# tr02.net
KiCad netlist of a schematic drawn in EAGLE
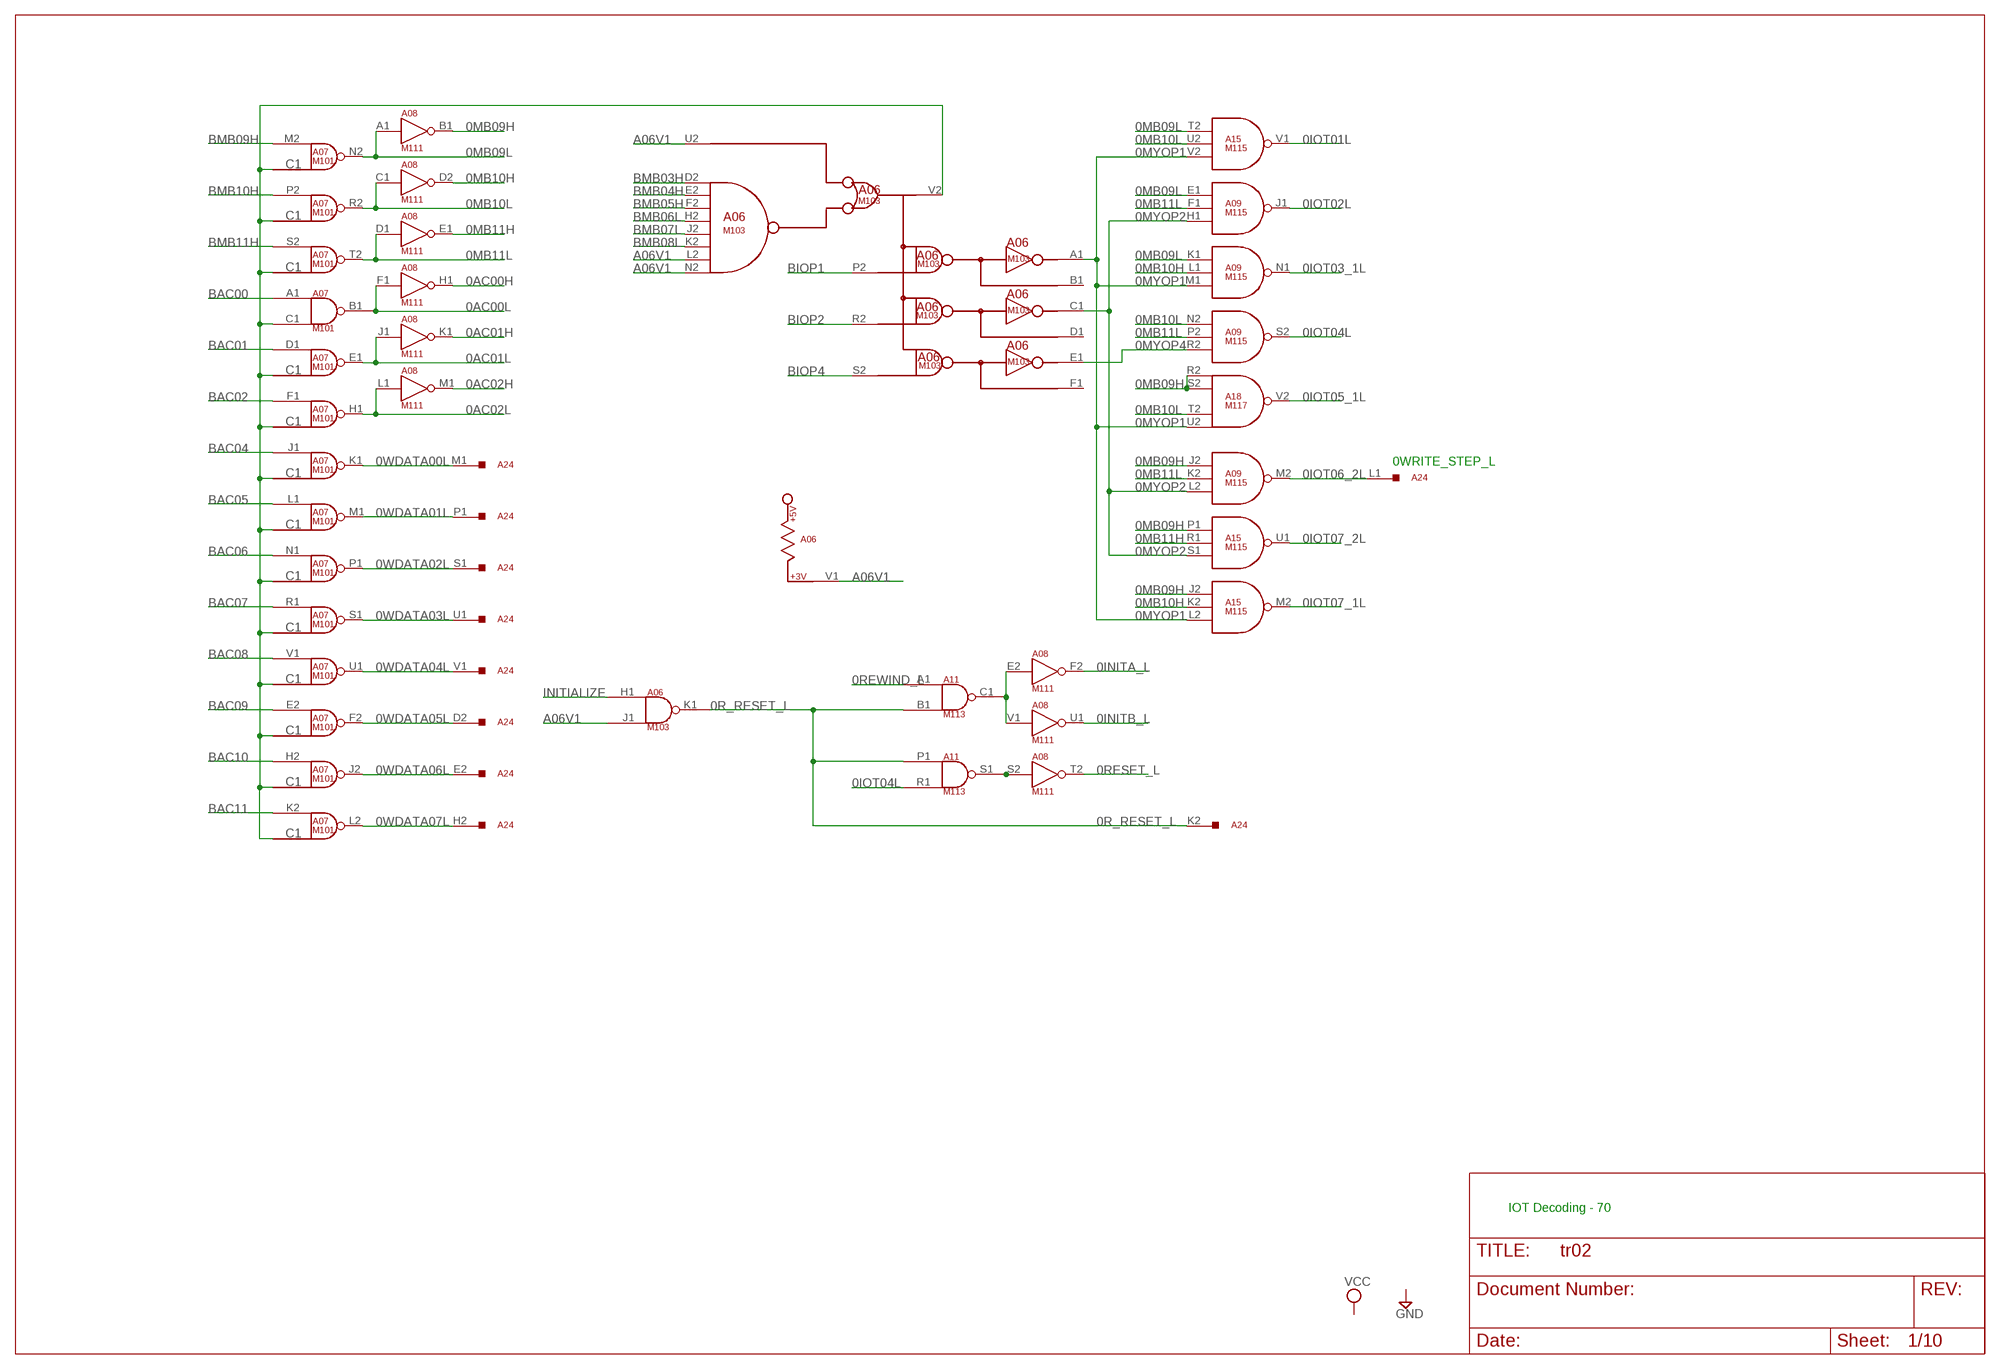
[diagram p0: schematic, sheet 1]
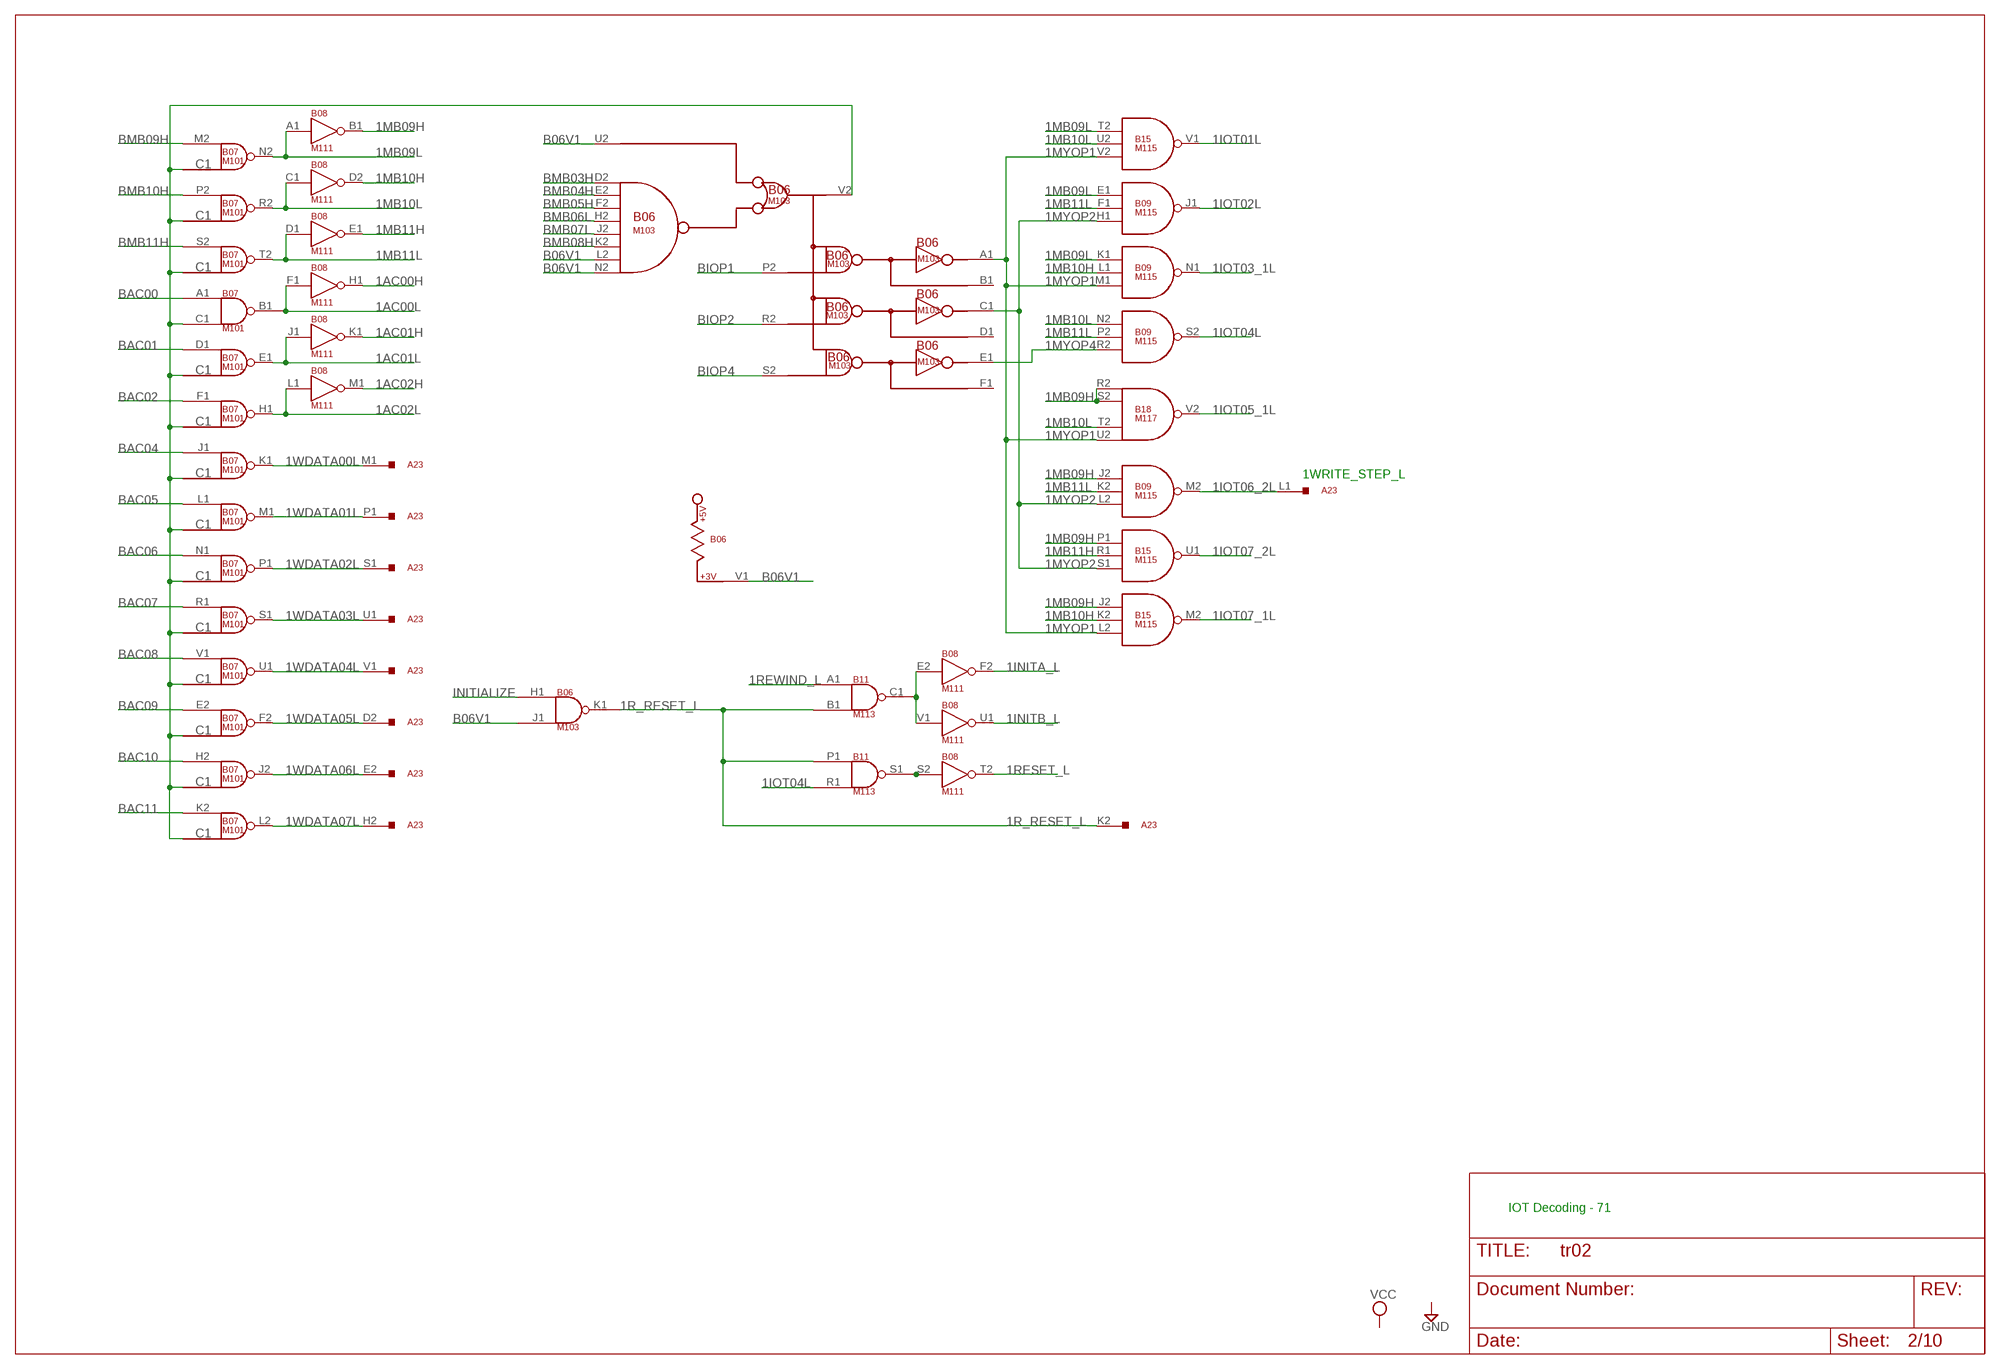
[diagram p1: schematic, sheet 2]
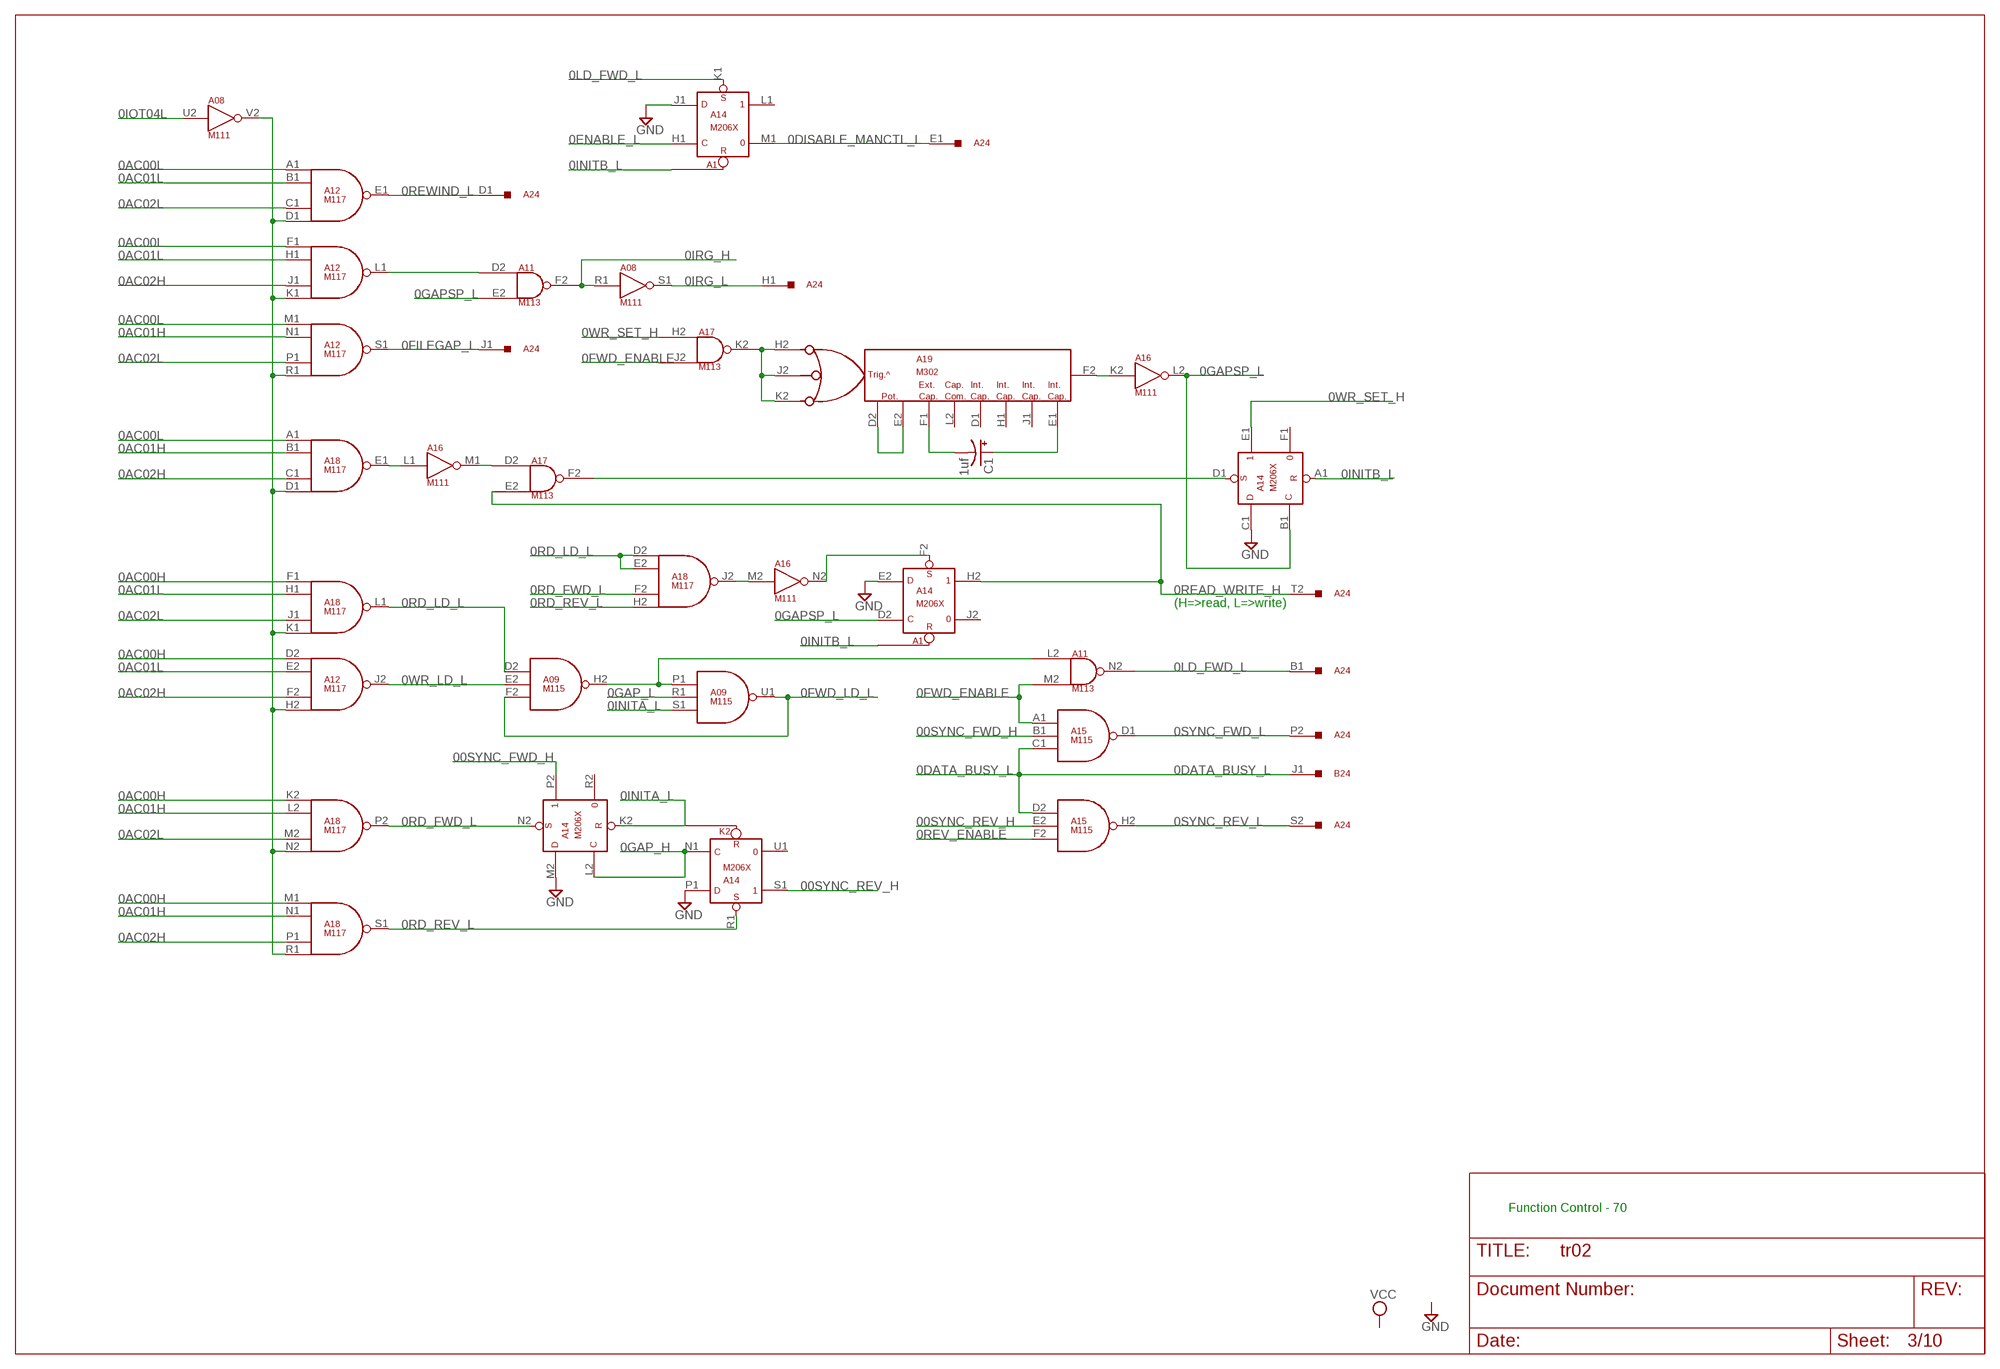
[diagram p2: schematic, sheet 3]
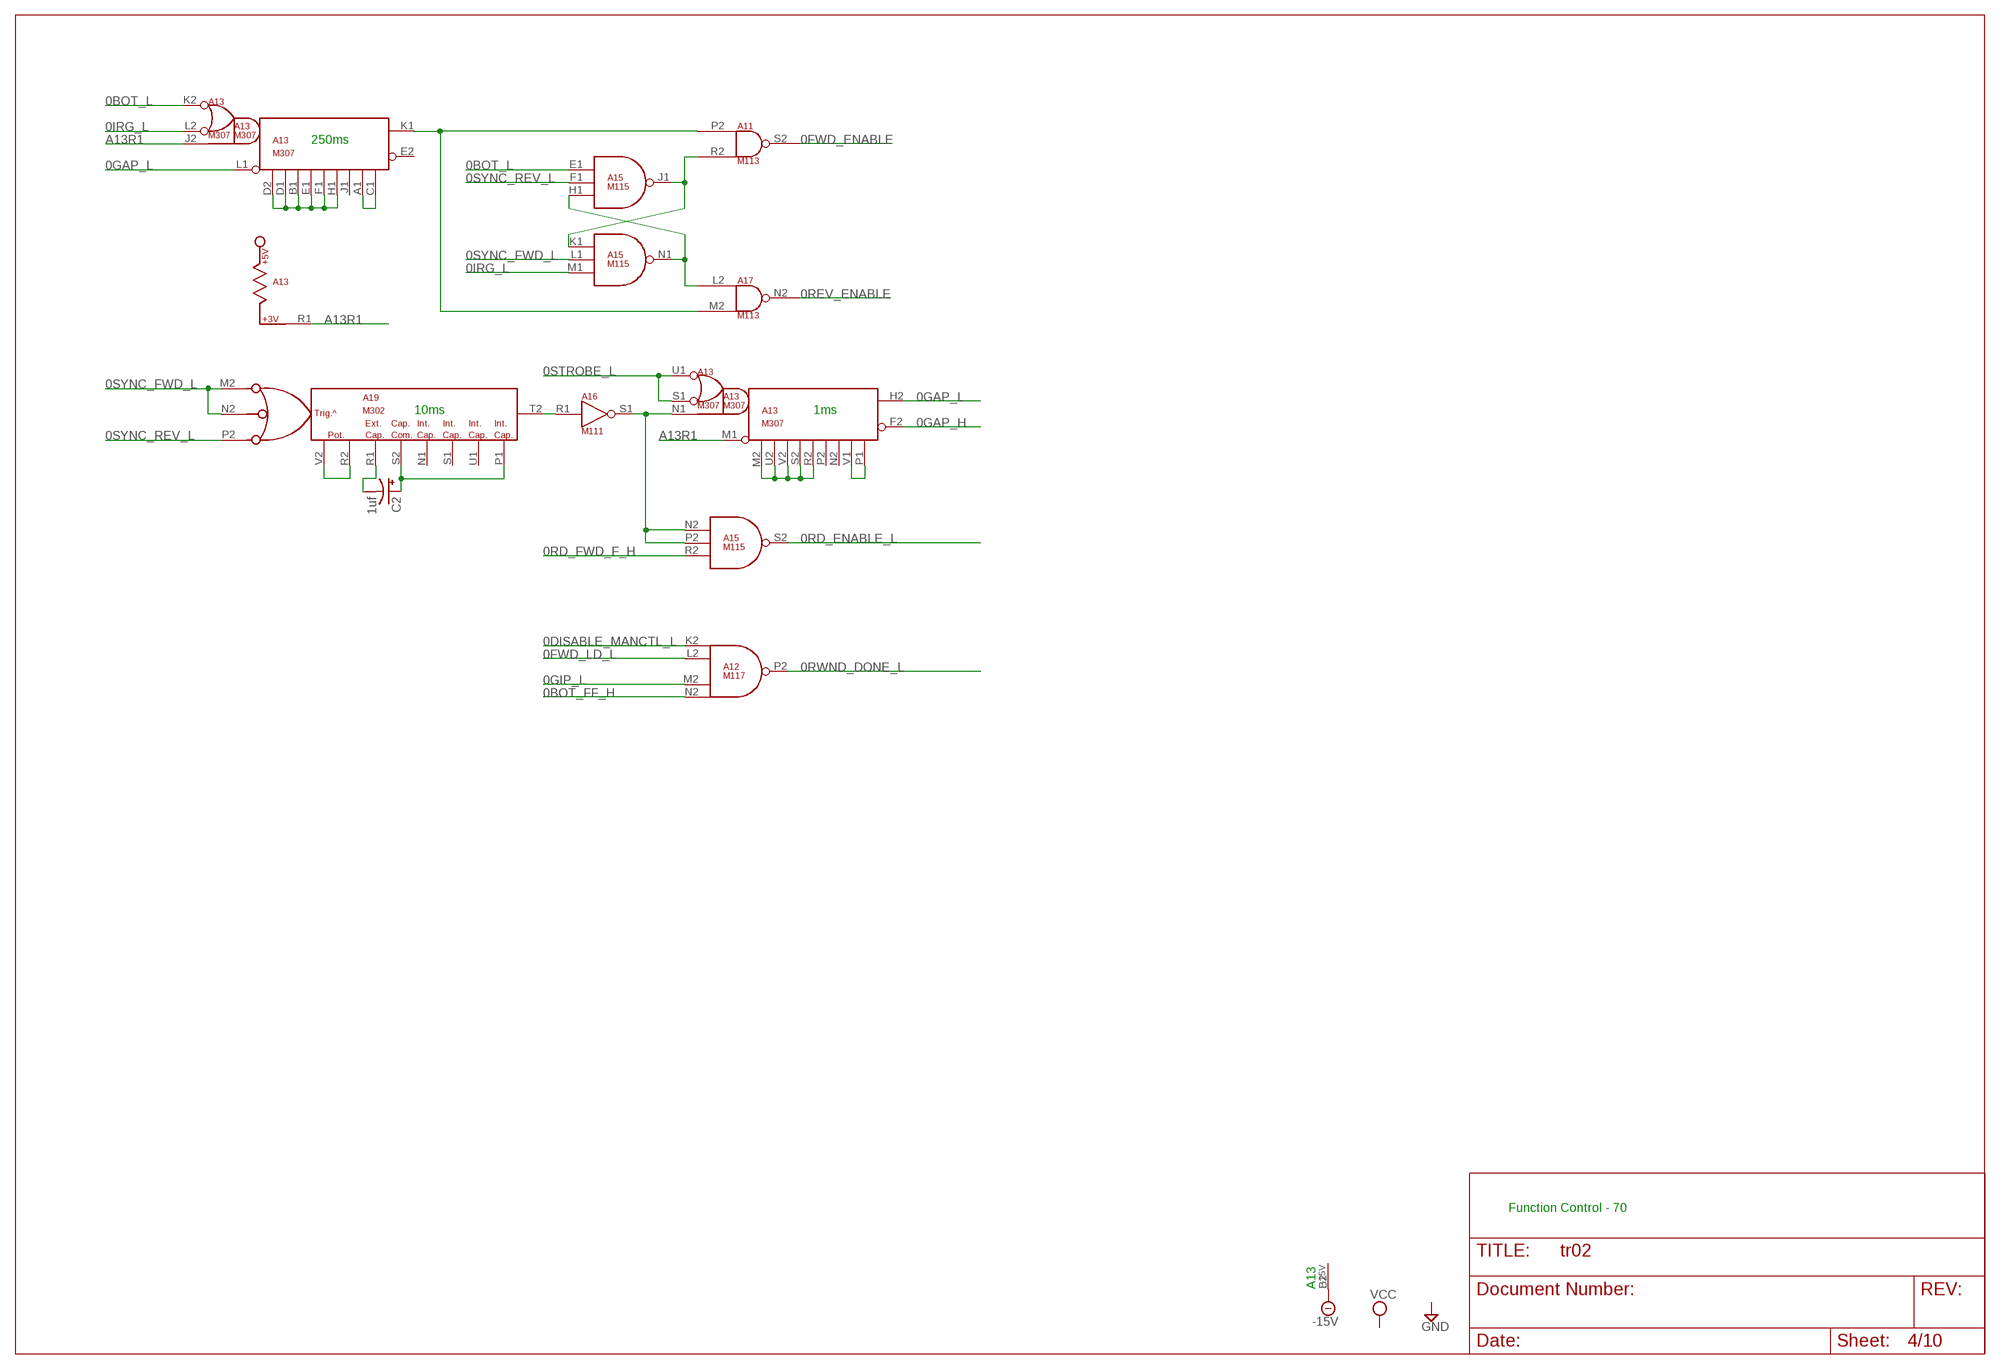
[diagram p3: schematic, sheet 4]
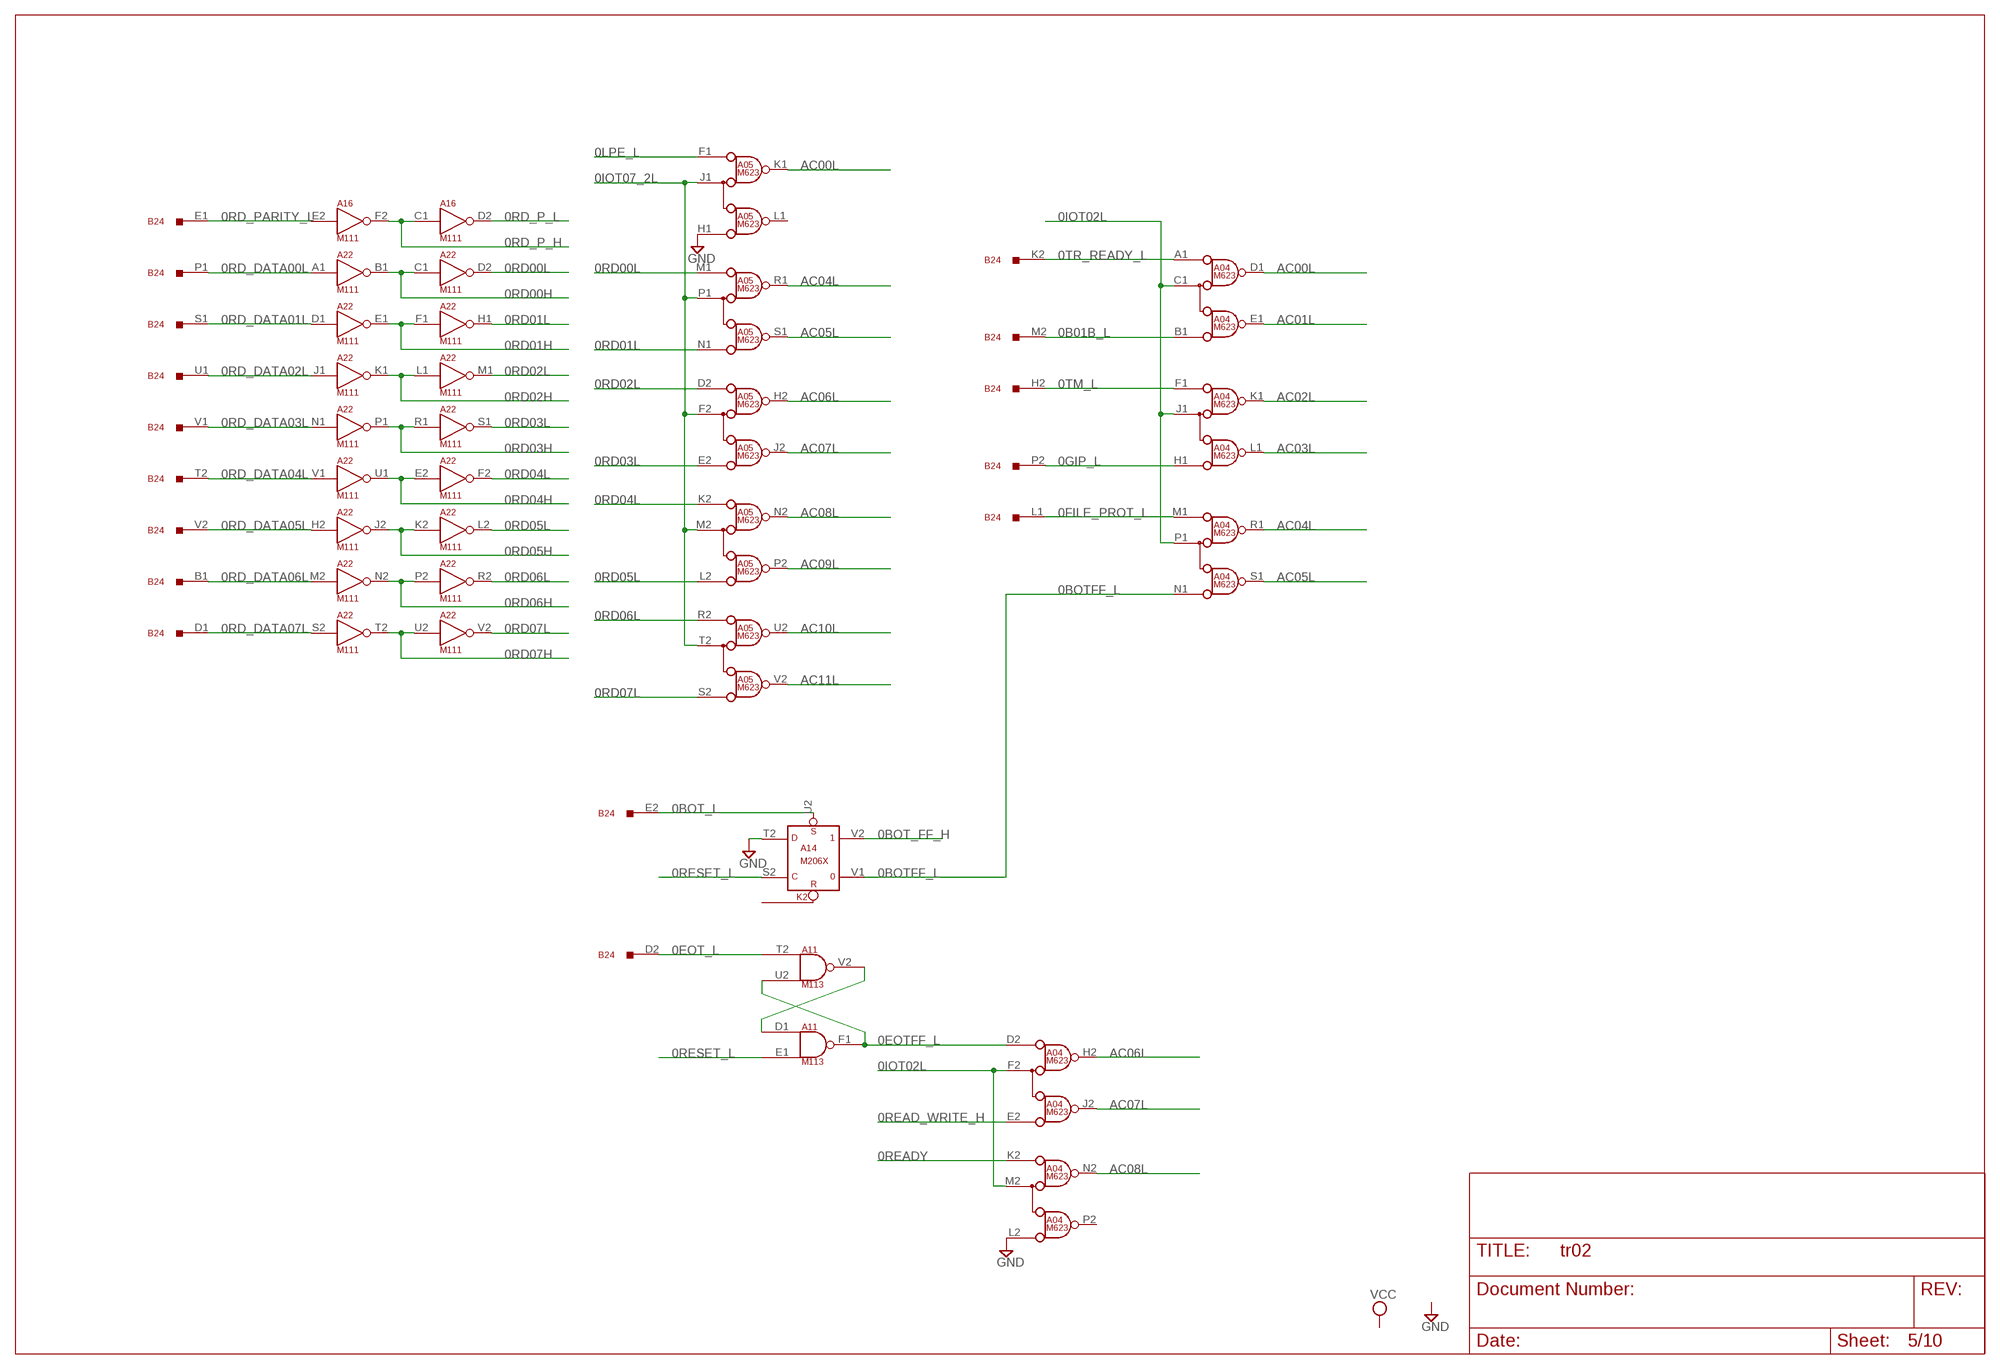
[diagram p4: schematic, sheet 5]
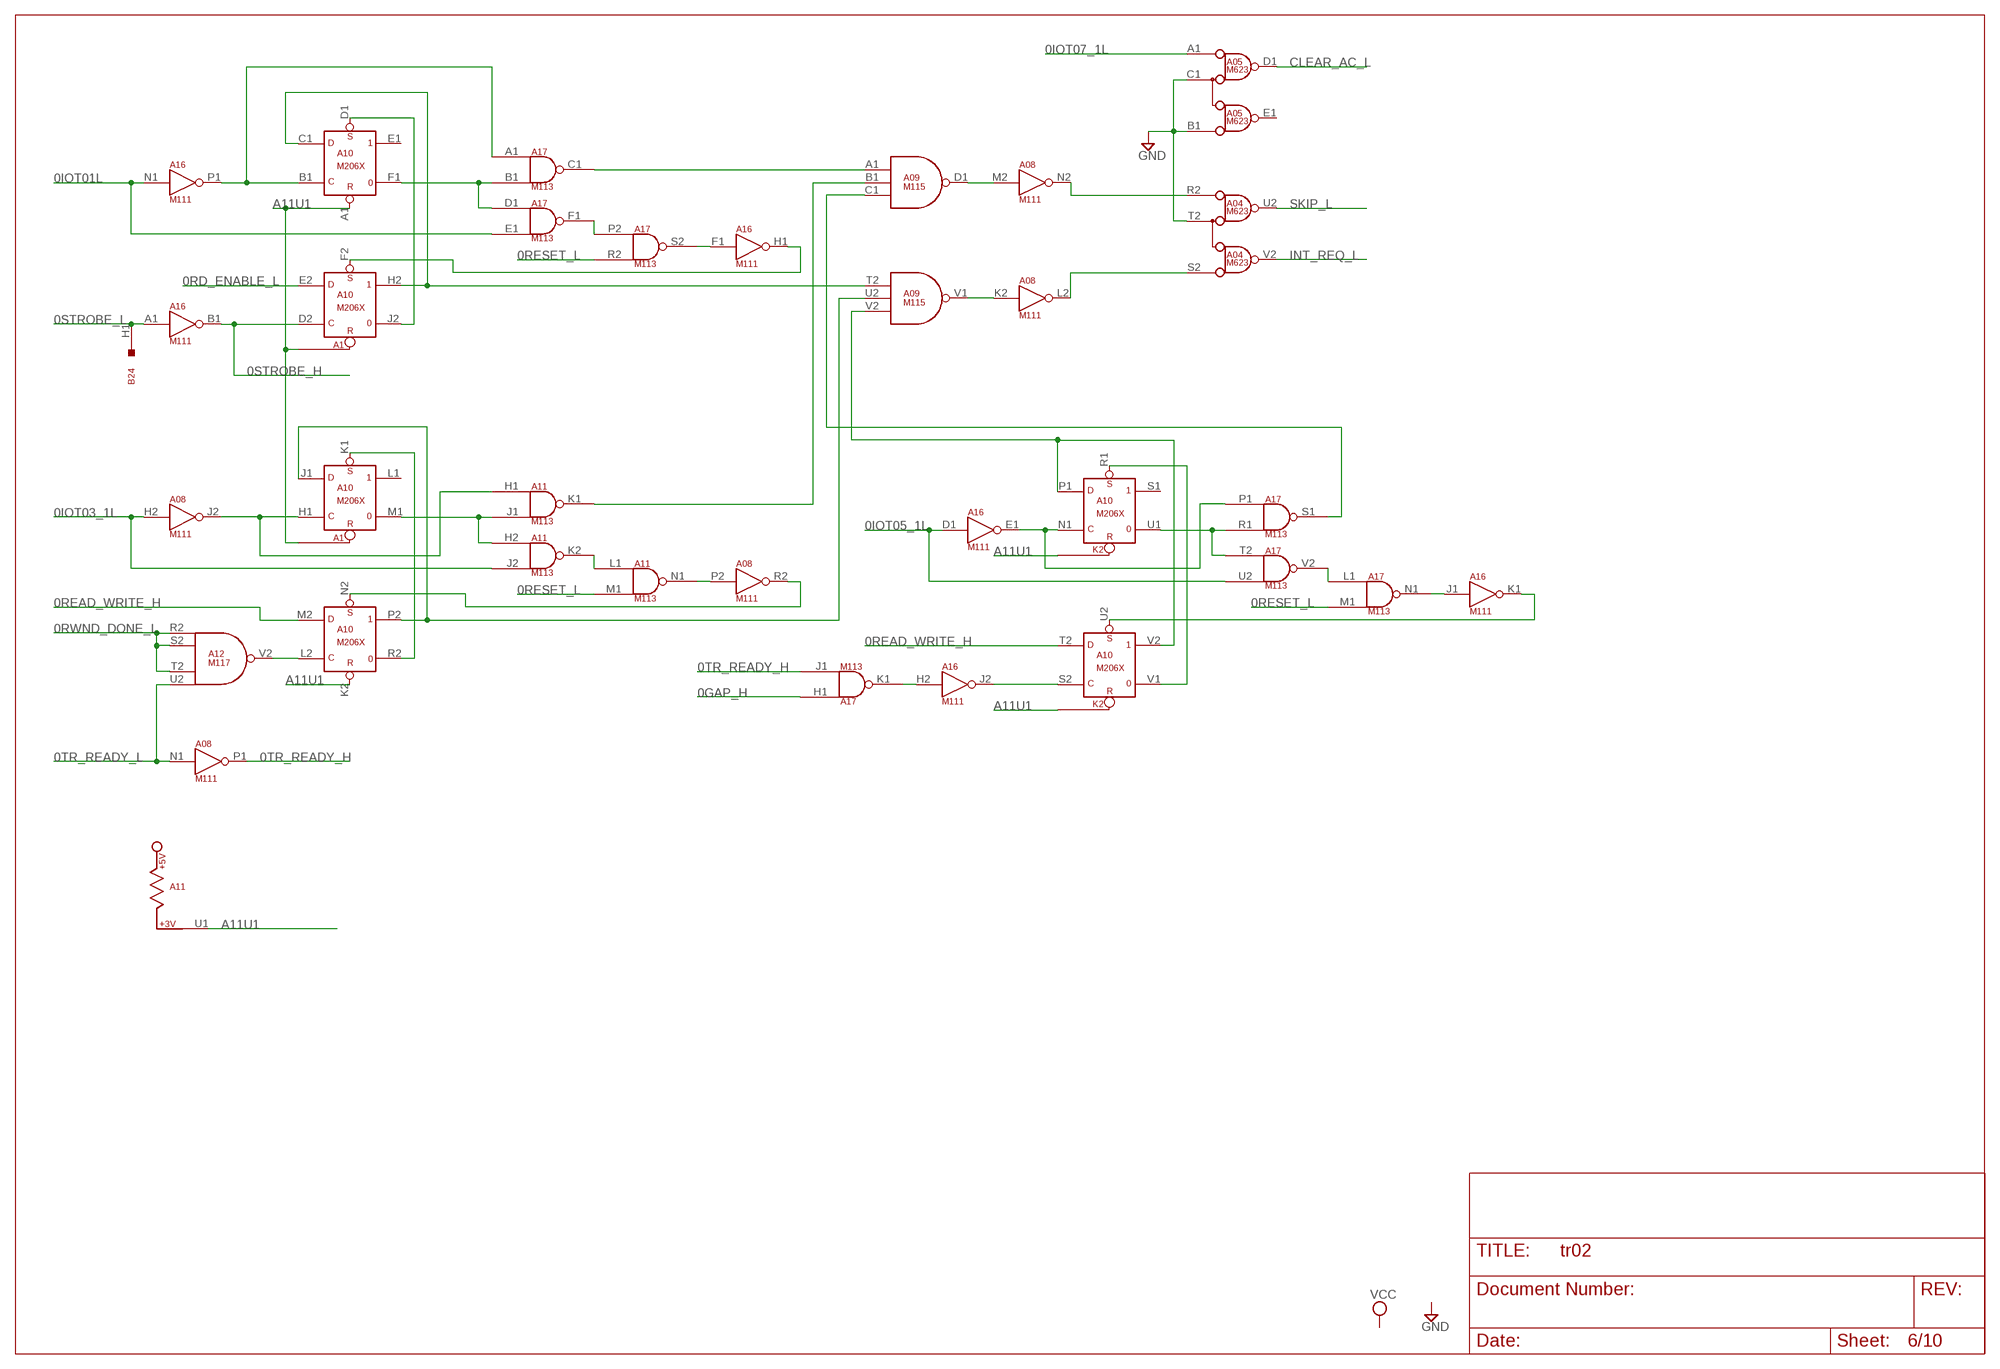
[diagram p5: schematic, sheet 6]
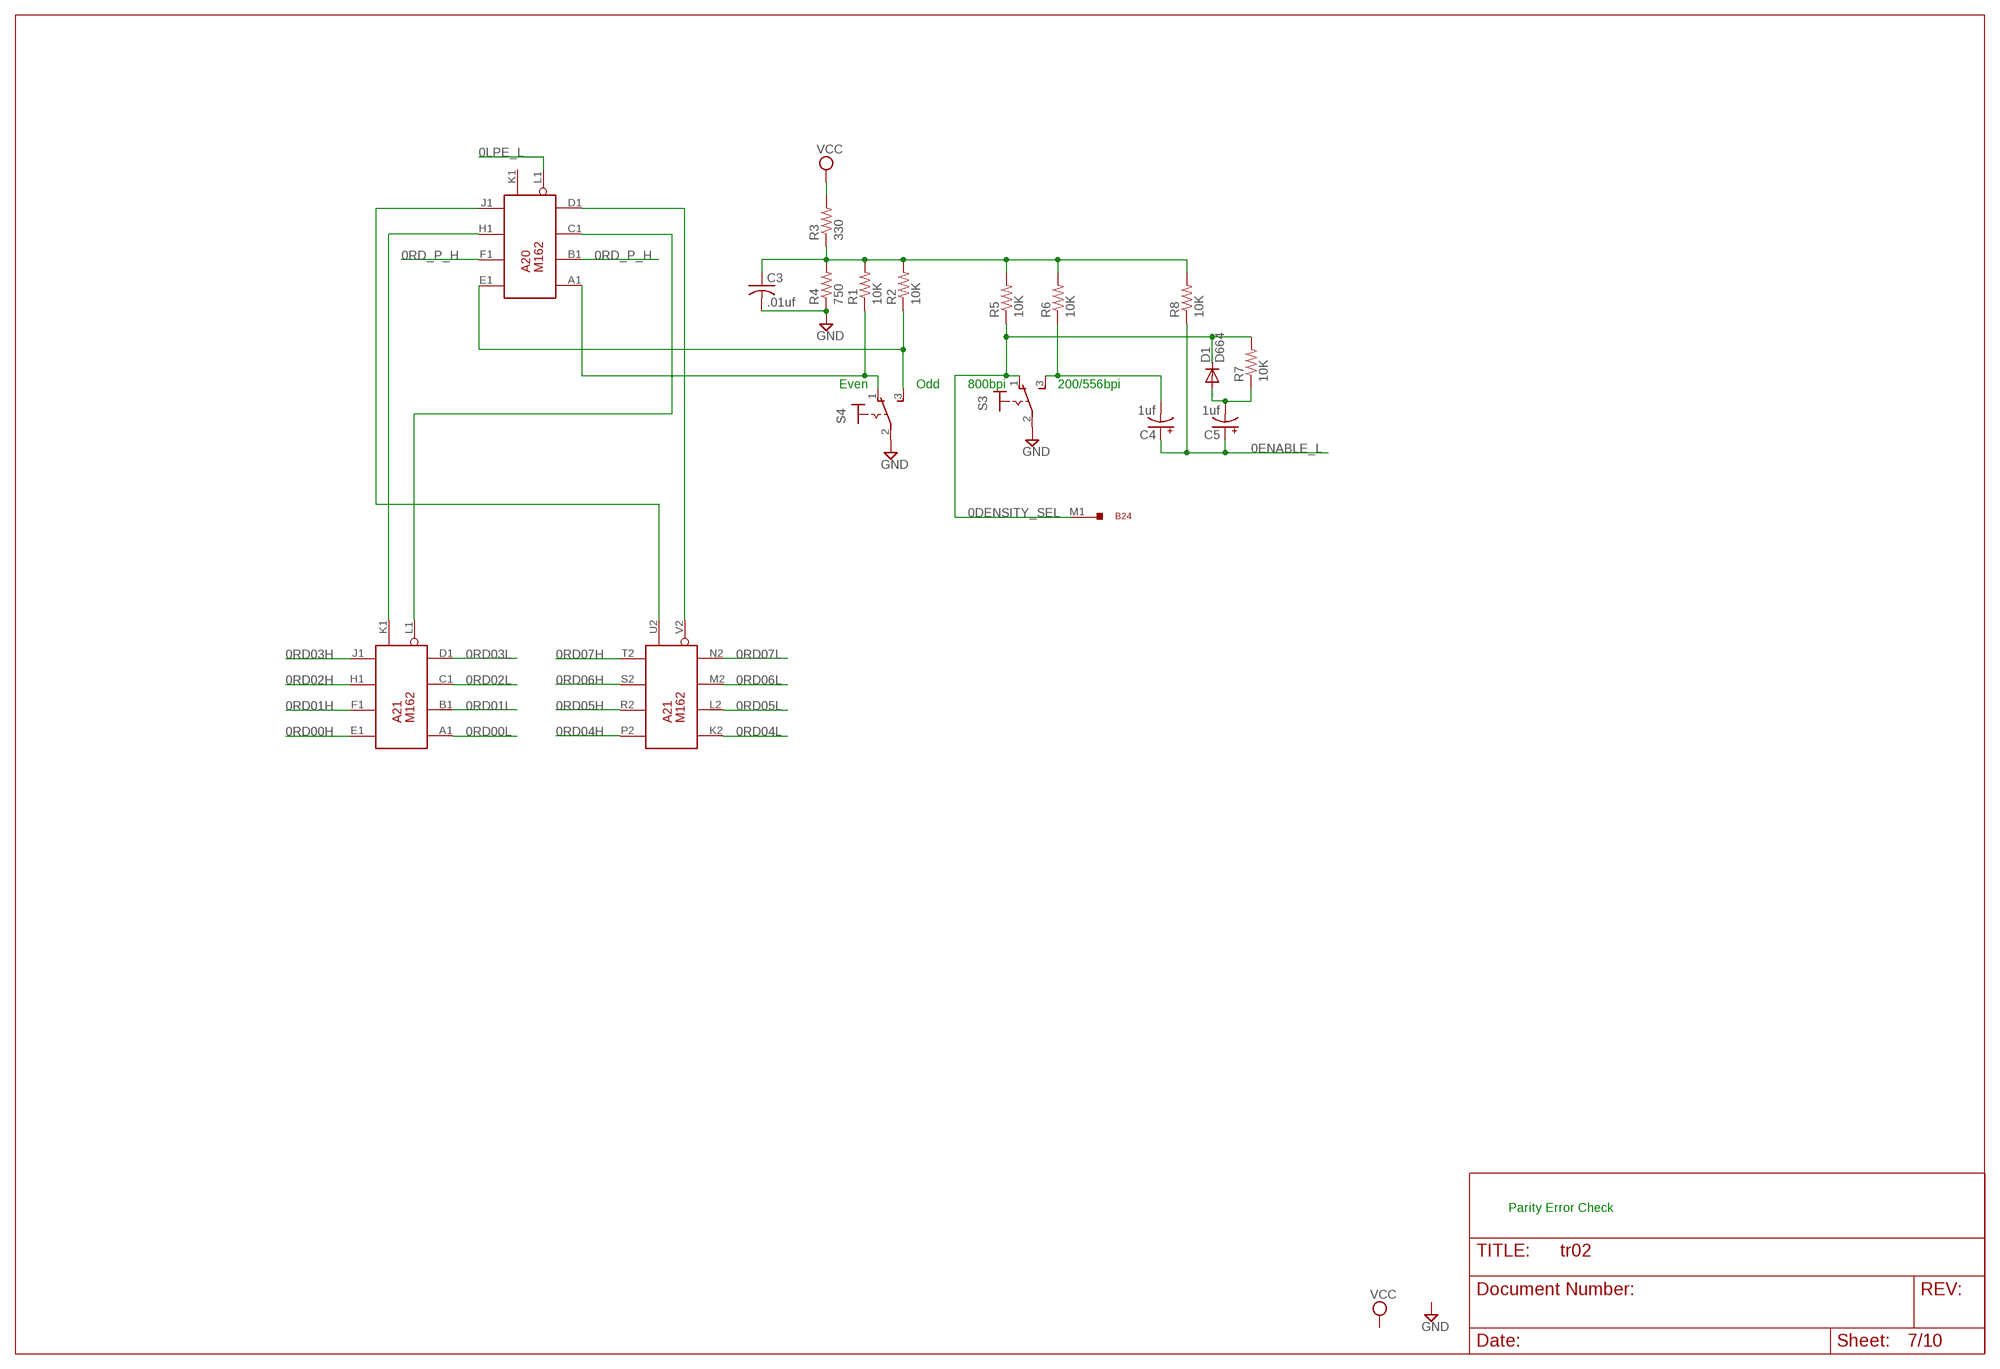
[diagram p6: schematic, sheet 7]
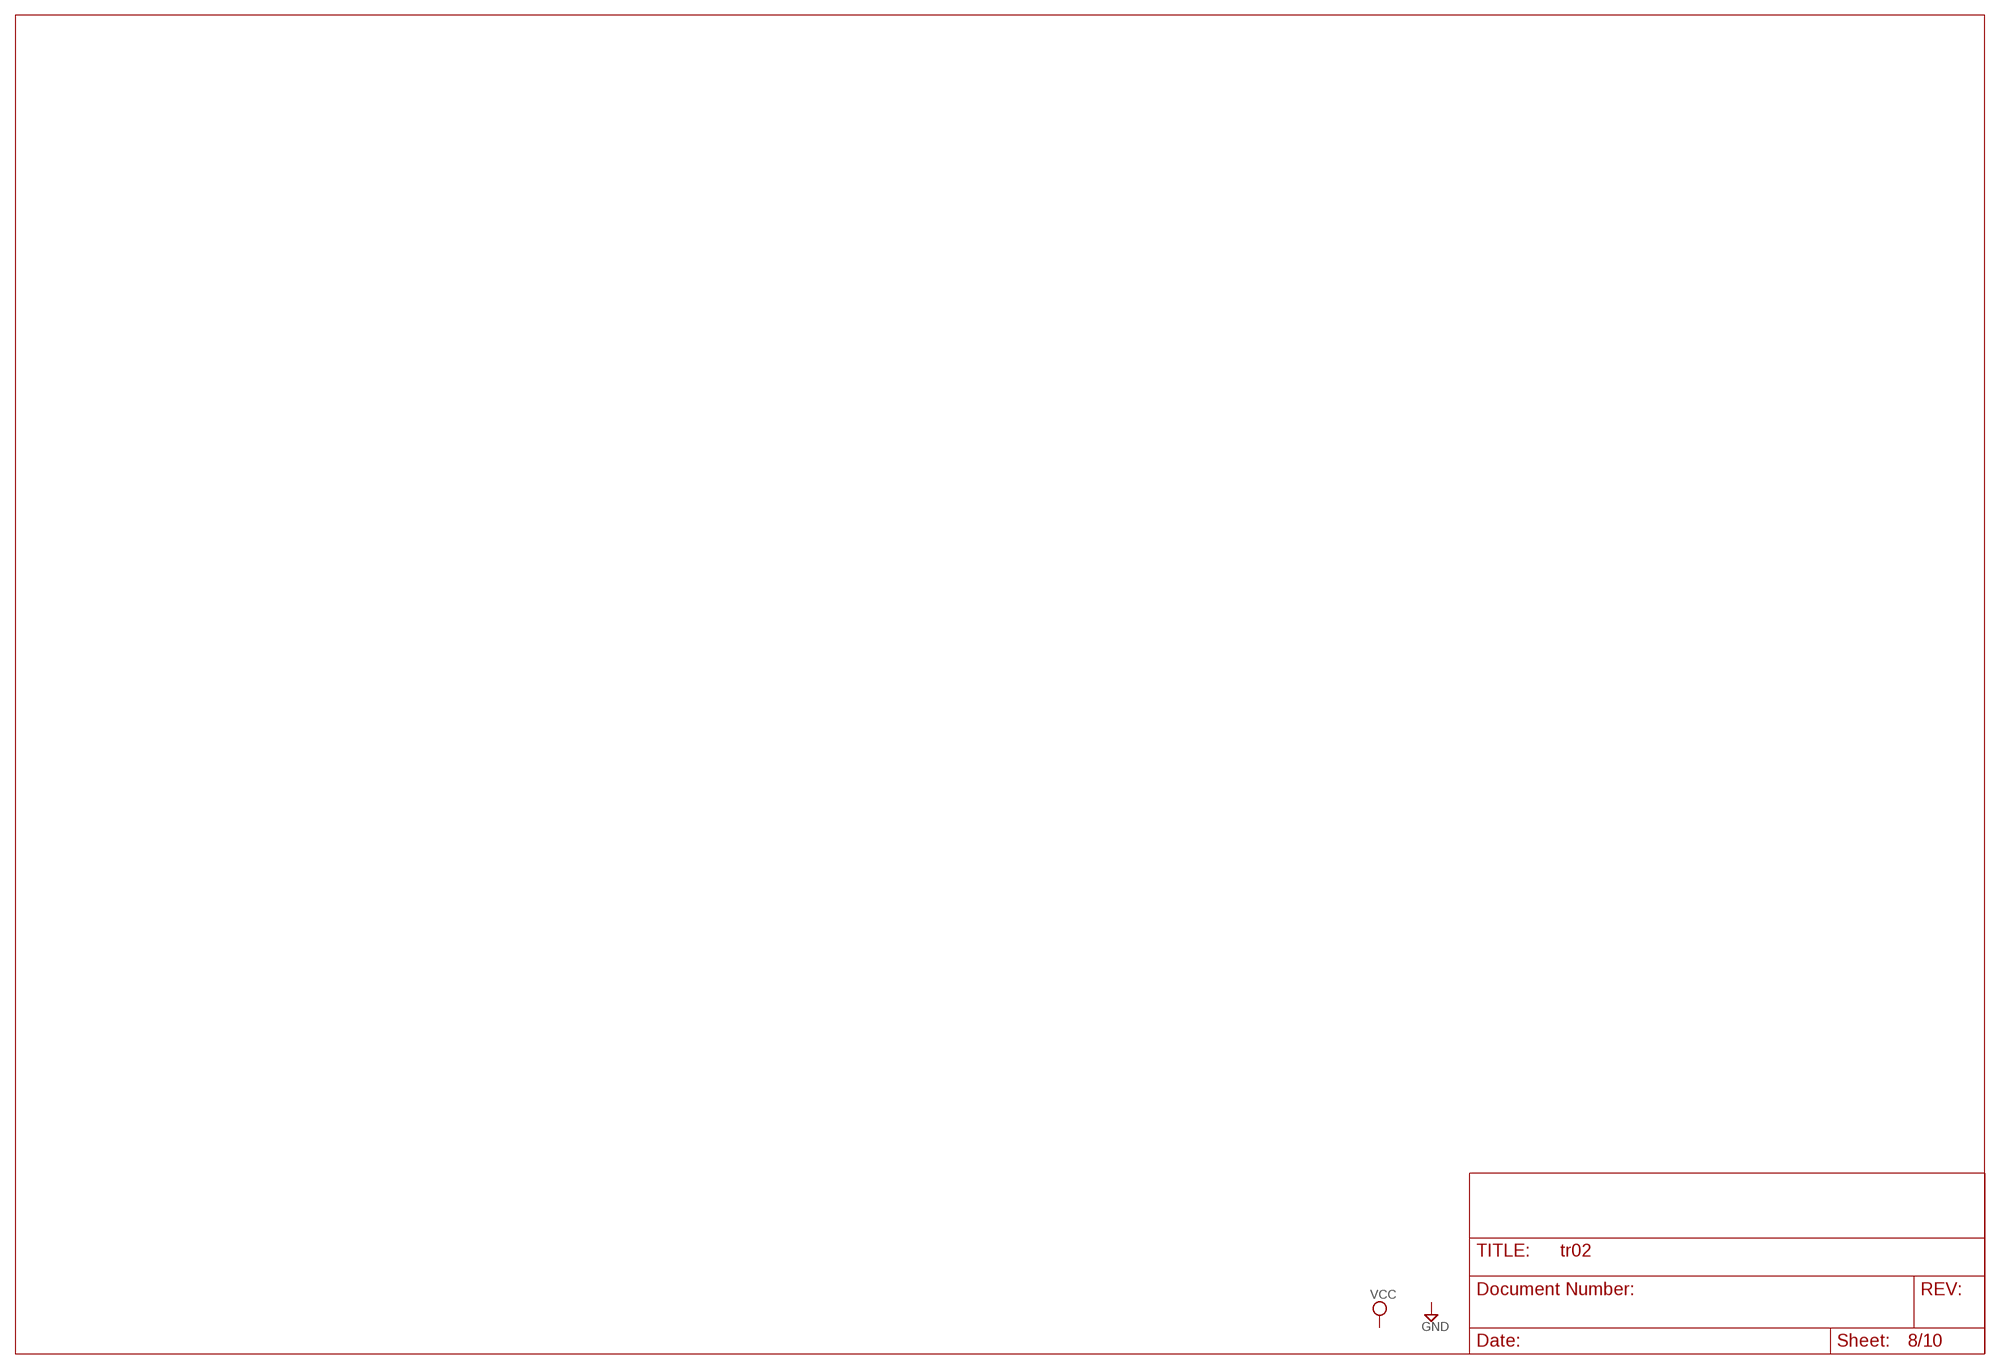
[diagram p7: schematic, sheet 8]
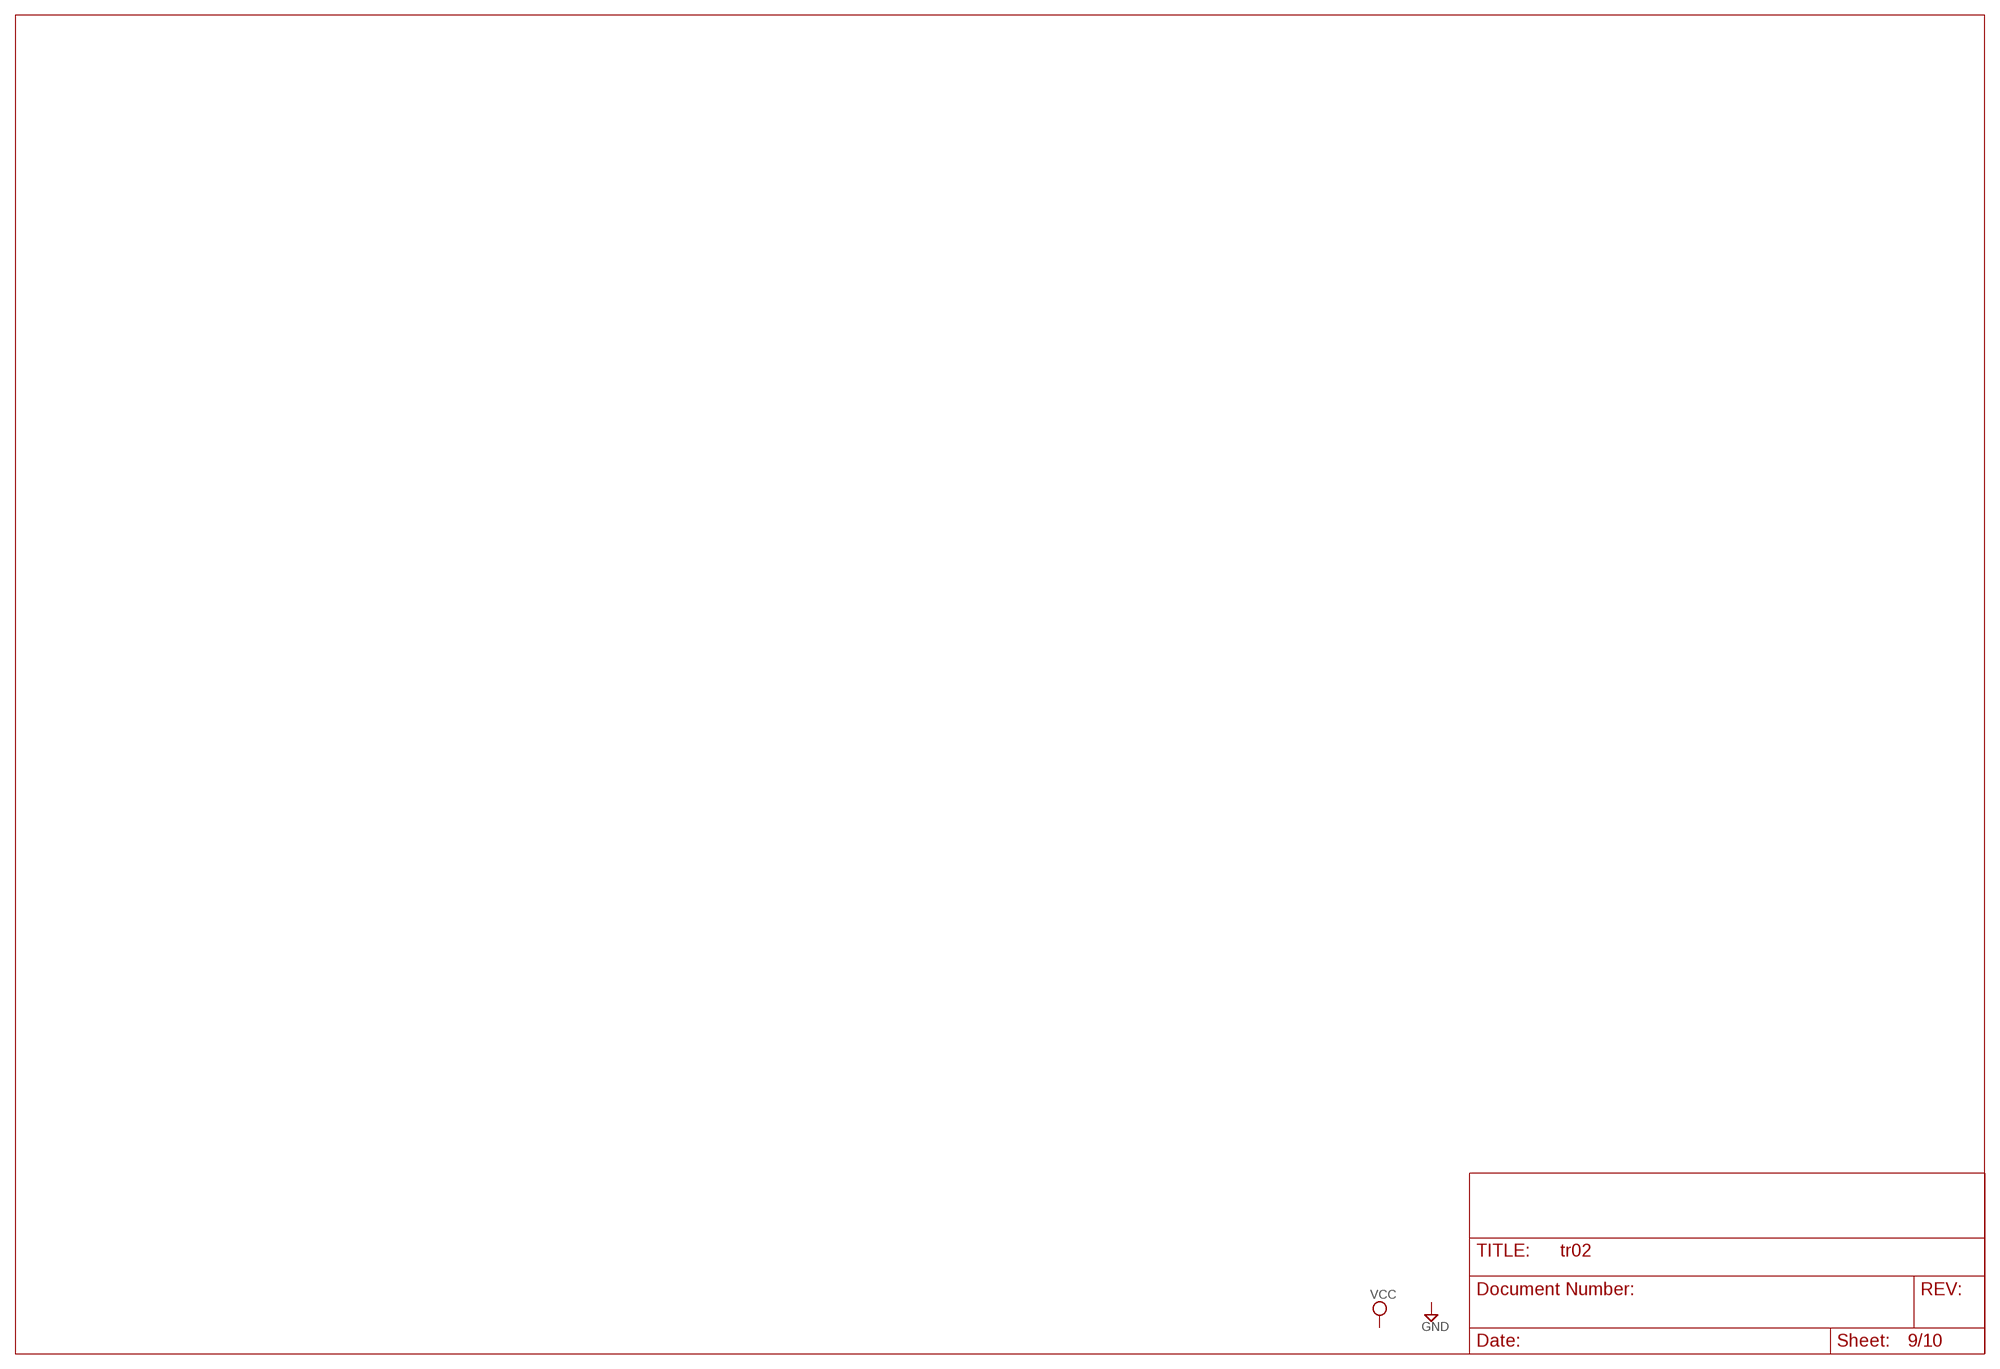
[diagram p8: schematic, sheet 9]
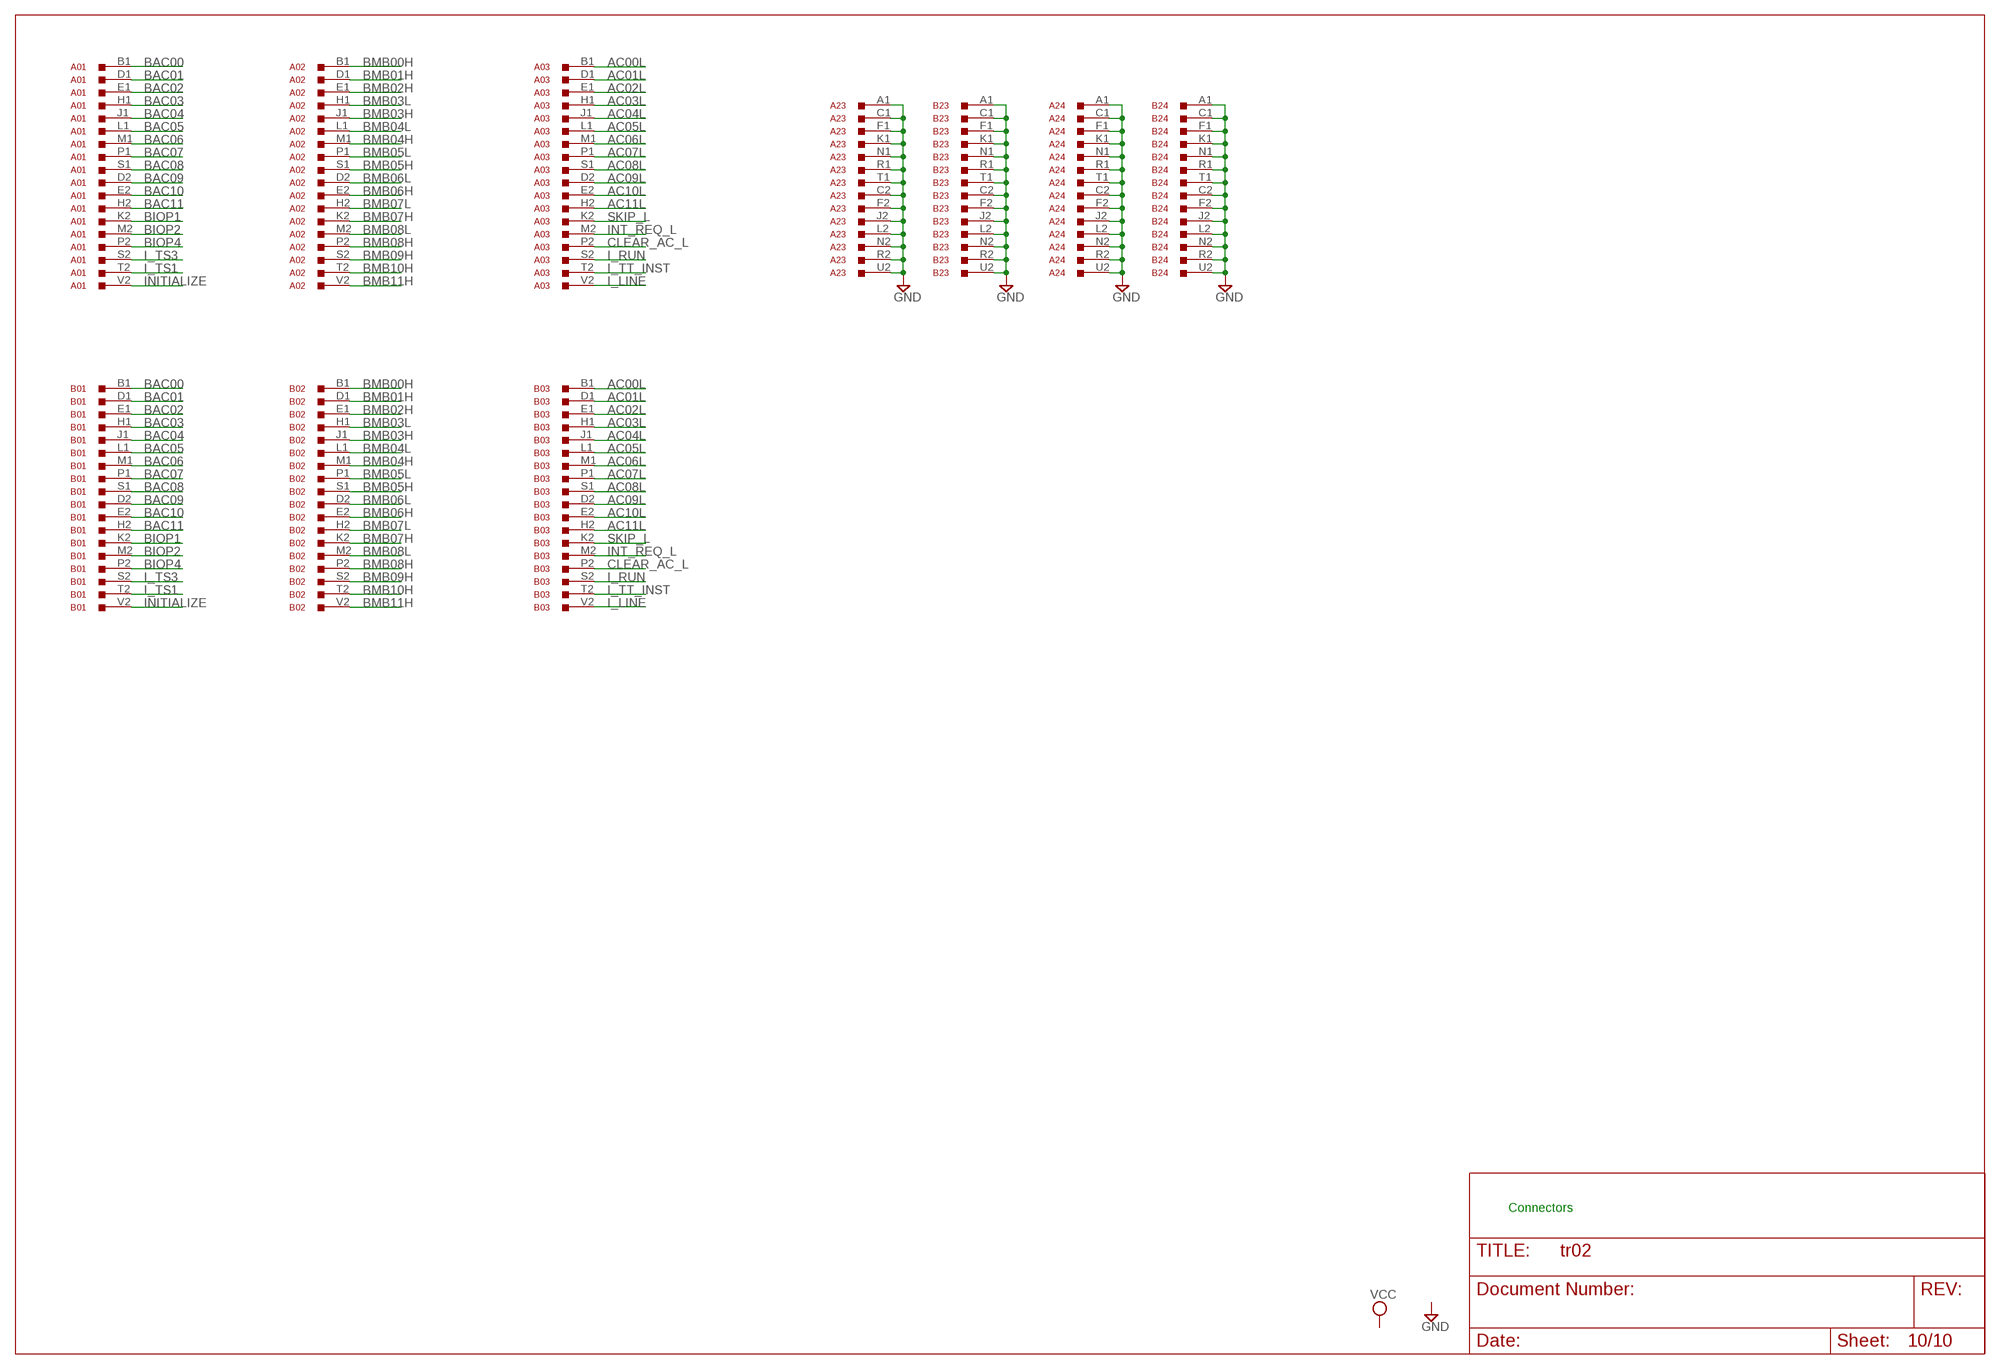
[diagram p9: schematic, sheet 10]

(export (version "E")
  (design (tool "Eeschema 10.0.6"))
  (components
    (comp (ref "A23")
      (value "G784")
      (footprint "eagle-import:H807")
      (libsource (lib "eagle-import") (part "M916"))
    )
    (comp (ref "B06")
      (value "M103")
      (footprint "eagle-import:H807")
      (libsource (lib "eagle-import") (part "M103"))
    )
    (comp (ref "B07")
      (value "M101")
      (footprint "eagle-import:H807")
      (libsource (lib "eagle-import") (part "M101"))
    )
    (comp (ref "B08")
      (value "M111")
      (footprint "eagle-import:H807")
      (libsource (lib "eagle-import") (part "M111"))
    )
    (comp (ref "B09")
      (value "M115")
      (footprint "eagle-import:H807")
      (libsource (lib "eagle-import") (part "M115"))
    )
    (comp (ref "B11")
      (value "M113")
      (footprint "eagle-import:H807")
      (libsource (lib "eagle-import") (part "M113"))
    )
    (comp (ref "B15")
      (value "M115")
      (footprint "eagle-import:H807")
      (libsource (lib "eagle-import") (part "M115"))
    )
    (comp (ref "B18")
      (value "M117")
      (footprint "eagle-import:H807")
      (libsource (lib "eagle-import") (part "M117"))
    )
    (comp (ref "A08")
      (value "M111")
      (footprint "eagle-import:H807")
      (libsource (lib "eagle-import") (part "M111"))
    )
    (comp (ref "A09")
      (value "M115")
      (footprint "eagle-import:H807")
      (libsource (lib "eagle-import") (part "M115"))
    )
    (comp (ref "A11")
      (value "M113")
      (footprint "eagle-import:H807")
      (libsource (lib "eagle-import") (part "M113"))
    )
    (comp (ref "A12")
      (value "M117")
      (footprint "eagle-import:H807")
      (libsource (lib "eagle-import") (part "M117"))
    )
    (comp (ref "A14")
      (value "M206X")
      (footprint "eagle-import:H807")
      (libsource (lib "eagle-import") (part "M206X"))
    )
    (comp (ref "A15")
      (value "M115")
      (footprint "eagle-import:H807")
      (libsource (lib "eagle-import") (part "M115"))
    )
    (comp (ref "A16")
      (value "M111")
      (footprint "eagle-import:H807")
      (libsource (lib "eagle-import") (part "M111"))
    )
    (comp (ref "A17")
      (value "M113")
      (footprint "eagle-import:H807")
      (libsource (lib "eagle-import") (part "M113"))
    )
    (comp (ref "A18")
      (value "M117")
      (footprint "eagle-import:H807")
      (libsource (lib "eagle-import") (part "M117"))
    )
    (comp (ref "A19")
      (value "M302")
      (footprint "eagle-import:H807")
      (libsource (lib "eagle-import") (part "M302"))
    )
    (comp (ref "A24")
      (value "G784")
      (footprint "eagle-import:H807")
      (libsource (lib "eagle-import") (part "M916"))
    )
    (comp (ref "B24")
      (value "G784")
      (footprint "eagle-import:H807")
      (libsource (lib "eagle-import") (part "M916"))
    )
    (comp (ref "C1")
      (value "1uf")
      (footprint "eagle-import:E22-6")
      (libsource (lib "eagle-import") (part "CPOL-USE22-6AXIAL"))
    )
    (comp (ref "A20")
      (value "M162")
      (footprint "eagle-import:H807")
      (libsource (lib "eagle-import") (part "M162"))
    )
    (comp (ref "A21")
      (value "M162")
      (footprint "eagle-import:H807")
      (libsource (lib "eagle-import") (part "M162"))
    )
    (comp (ref "C3")
      (value ".01uf")
      (footprint "eagle-import:C050-025X075")
      (libsource (lib "eagle-import") (part "C-US050-025X075"))
    )
    (comp (ref "C4")
      (value "1uf")
      (footprint "eagle-import:E22-6")
      (libsource (lib "eagle-import") (part "CPOL-USE22-6AXIAL"))
    )
    (comp (ref "C5")
      (value "1uf")
      (footprint "eagle-import:E22-6")
      (libsource (lib "eagle-import") (part "CPOL-USE22-6AXIAL"))
    )
    (comp (ref "D1")
      (value "D664")
      (footprint "eagle-import:DO35-10")
      (libsource (lib "eagle-import") (part "1N4148DO35-10"))
    )
    (comp (ref "R1")
      (value "10K")
      (footprint "eagle-import:0207_10")
      (libsource (lib "eagle-import") (part "R-US_0207/10"))
    )
    (comp (ref "R2")
      (value "10K")
      (footprint "eagle-import:0207_10")
      (libsource (lib "eagle-import") (part "R-US_0207/10"))
    )
    (comp (ref "R3")
      (value "330")
      (footprint "eagle-import:0207_10")
      (libsource (lib "eagle-import") (part "R-US_0207/10"))
    )
    (comp (ref "R4")
      (value "750")
      (footprint "eagle-import:0207_10")
      (libsource (lib "eagle-import") (part "R-US_0207/10"))
    )
    (comp (ref "R5")
      (value "10K")
      (footprint "eagle-import:0207_10")
      (libsource (lib "eagle-import") (part "R-US_0207/10"))
    )
    (comp (ref "R6")
      (value "10K")
      (footprint "eagle-import:0207_10")
      (libsource (lib "eagle-import") (part "R-US_0207/10"))
    )
    (comp (ref "R7")
      (value "10K")
      (footprint "eagle-import:0207_10")
      (libsource (lib "eagle-import") (part "R-US_0207/10"))
    )
    (comp (ref "R8")
      (value "10K")
      (footprint "eagle-import:0207_10")
      (libsource (lib "eagle-import") (part "R-US_0207/10"))
    )
    (comp (ref "S3")
      (value "320-916")
      (footprint "eagle-import:320-916")
      (libsource (lib "eagle-import") (part "320-916"))
    )
    (comp (ref "S4")
      (value "320-916")
      (footprint "eagle-import:320-916")
      (libsource (lib "eagle-import") (part "320-916"))
    )
    (comp (ref "A04")
      (value "M623")
      (footprint "eagle-import:H807")
      (libsource (lib "eagle-import") (part "M623"))
    )
    (comp (ref "A05")
      (value "M623")
      (footprint "eagle-import:H807")
      (libsource (lib "eagle-import") (part "M623"))
    )
    (comp (ref "A10")
      (value "M206X")
      (footprint "eagle-import:H807")
      (libsource (lib "eagle-import") (part "M206X"))
    )
    (comp (ref "A01")
      (value "M903")
      (footprint "eagle-import:H807")
      (libsource (lib "eagle-import") (part "M903"))
    )
    (comp (ref "A02")
      (value "M903")
      (footprint "eagle-import:H807")
      (libsource (lib "eagle-import") (part "M903"))
    )
    (comp (ref "A03")
      (value "M903")
      (footprint "eagle-import:H807")
      (libsource (lib "eagle-import") (part "M903"))
    )
    (comp (ref "B01")
      (value "M903")
      (footprint "eagle-import:H807")
      (libsource (lib "eagle-import") (part "M903"))
    )
    (comp (ref "B02")
      (value "M903")
      (footprint "eagle-import:H807")
      (libsource (lib "eagle-import") (part "M903"))
    )
    (comp (ref "B03")
      (value "M903")
      (footprint "eagle-import:H807")
      (libsource (lib "eagle-import") (part "M903"))
    )
    (comp (ref "B23")
      (value "G784")
      (footprint "eagle-import:H807")
      (libsource (lib "eagle-import") (part "M916"))
    )
    (comp (ref "A06")
      (value "M103")
      (footprint "eagle-import:H807")
      (libsource (lib "eagle-import") (part "M103"))
    )
    (comp (ref "A07")
      (value "M101")
      (footprint "eagle-import:H807")
      (libsource (lib "eagle-import") (part "M101"))
    )
    (comp (ref "A13")
      (value "M307")
      (footprint "eagle-import:H807")
      (libsource (lib "eagle-import") (part "M307"))
    )
    (comp (ref "C2")
      (value "1uf")
      (footprint "eagle-import:E22-6")
      (libsource (lib "eagle-import") (part "CPOL-USE22-6AXIAL"))
    )
    (comp (ref "A22")
      (value "M111")
      (footprint "eagle-import:H807")
      (libsource (lib "eagle-import") (part "M111"))
    )
  )
  (nets
    (net (code "1") (name "-15V") (class "Default")
      (node (ref "A13") (pin "B2") (pinfunction "-15V_B2") (pintype "power_in"))
    )
    (net (code "2") (name "0AC00H") (class "Default")
      (node (ref "A08") (pin "H1") (pinfunction "OUT_H1") (pintype "output"))
      (node (ref "A12") (pin "D2") (pinfunction "IN1_D2") (pintype "input"))
      (node (ref "A18") (pin "F1") (pinfunction "IN1_F1") (pintype "input"))
      (node (ref "A18") (pin "K2") (pinfunction "IN1_K2") (pintype "input"))
      (node (ref "A18") (pin "M1") (pinfunction "IN1_M1") (pintype "input"))
    )
    (net (code "3") (name "0AC00L") (class "Default")
      (node (ref "A07") (pin "B1") (pinfunction "OUT_B1") (pintype "output"))
      (node (ref "A08") (pin "F1") (pinfunction "IN_F1") (pintype "input"))
      (node (ref "A12") (pin "A1") (pinfunction "IN1_A1") (pintype "input"))
      (node (ref "A12") (pin "F1") (pinfunction "IN1_F1") (pintype "input"))
      (node (ref "A12") (pin "M1") (pinfunction "IN1_M1") (pintype "input"))
      (node (ref "A18") (pin "A1") (pinfunction "IN1_A1") (pintype "input"))
    )
    (net (code "4") (name "0AC01H") (class "Default")
      (node (ref "A08") (pin "K1") (pinfunction "OUT_K1") (pintype "output"))
      (node (ref "A12") (pin "N1") (pinfunction "IN2_N1") (pintype "input"))
      (node (ref "A18") (pin "B1") (pinfunction "IN2_B1") (pintype "input"))
      (node (ref "A18") (pin "L2") (pinfunction "IN2_L2") (pintype "input"))
      (node (ref "A18") (pin "N1") (pinfunction "IN2_N1") (pintype "input"))
    )
    (net (code "5") (name "0AC01L") (class "Default")
      (node (ref "A07") (pin "E1") (pinfunction "OUT_E1") (pintype "output"))
      (node (ref "A08") (pin "J1") (pinfunction "IN_J1") (pintype "input"))
      (node (ref "A12") (pin "B1") (pinfunction "IN2_B1") (pintype "input"))
      (node (ref "A12") (pin "E2") (pinfunction "IN2_E2") (pintype "input"))
      (node (ref "A12") (pin "H1") (pinfunction "IN2_H1") (pintype "input"))
      (node (ref "A18") (pin "H1") (pinfunction "IN2_H1") (pintype "input"))
    )
    (net (code "6") (name "0AC02H") (class "Default")
      (node (ref "A08") (pin "M1") (pinfunction "OUT_M1") (pintype "output"))
      (node (ref "A12") (pin "F2") (pinfunction "IN3_F2") (pintype "input"))
      (node (ref "A12") (pin "J1") (pinfunction "IN3_J1") (pintype "input"))
      (node (ref "A18") (pin "C1") (pinfunction "IN3_C1") (pintype "input"))
      (node (ref "A18") (pin "P1") (pinfunction "IN3_P1") (pintype "input"))
    )
    (net (code "7") (name "0AC02L") (class "Default")
      (node (ref "A07") (pin "H1") (pinfunction "OUT_H1") (pintype "output"))
      (node (ref "A08") (pin "L1") (pinfunction "IN_L1") (pintype "input"))
      (node (ref "A12") (pin "C1") (pinfunction "IN3_C1") (pintype "input"))
      (node (ref "A12") (pin "P1") (pinfunction "IN3_P1") (pintype "input"))
      (node (ref "A18") (pin "J1") (pinfunction "IN3_J1") (pintype "input"))
      (node (ref "A18") (pin "M2") (pinfunction "IN3_M2") (pintype "input"))
    )
    (net (code "8") (name "0B01B_L") (class "Default")
      (node (ref "A04") (pin "B1") (pinfunction "B_B1") (pintype "input"))
      (node (ref "B24") (pin "M2") (pinfunction "P$2_M2") (pintype "bidirectional"))
    )
    (net (code "9") (name "0BOTFF_L") (class "Default")
      (node (ref "A04") (pin "N1") (pinfunction "B_N1") (pintype "input"))
      (node (ref "A14") (pin "V1") (pinfunction "0_V1") (pintype "output"))
    )
    (net (code "10") (name "0BOT_FF_H") (class "Default")
      (node (ref "A12") (pin "N2") (pinfunction "IN4_N2") (pintype "input"))
      (node (ref "A14") (pin "V2") (pinfunction "1_V2") (pintype "output"))
    )
    (net (code "11") (name "0BOT_L") (class "Default")
      (node (ref "A13") (pin "K2") (pinfunction "U1_K2") (pintype "input"))
      (node (ref "A14") (pin "U2") (pinfunction "S_U2") (pintype "input"))
      (node (ref "A15") (pin "E1") (pinfunction "IN1_E1") (pintype "input"))
      (node (ref "B24") (pin "E2") (pinfunction "P$2_E2") (pintype "bidirectional"))
    )
    (net (code "12") (name "0DATA_BUSY_L") (class "Default")
      (node (ref "A15") (pin "C1") (pinfunction "IN3_C1") (pintype "input"))
      (node (ref "A15") (pin "D2") (pinfunction "IN1_D2") (pintype "input"))
      (node (ref "B24") (pin "J1") (pinfunction "P$2_J1") (pintype "bidirectional"))
    )
    (net (code "13") (name "0DENSITY_SEL") (class "Default")
      (node (ref "B24") (pin "M1") (pinfunction "P$2_M1") (pintype "bidirectional"))
      (node (ref "D1") (pin "C") (pinfunction "C_C") (pintype "passive"))
      (node (ref "R5") (pin "1") (pinfunction "1_1") (pintype "passive"))
      (node (ref "R7") (pin "2") (pinfunction "2_2") (pintype "passive"))
      (node (ref "S3") (pin "1") (pinfunction "O_1") (pintype "passive"))
    )
    (net (code "14") (name "0DISABLE_MANCTL_L") (class "Default")
      (node (ref "A12") (pin "K2") (pinfunction "IN1_K2") (pintype "input"))
      (node (ref "A14") (pin "M1") (pinfunction "0_M1") (pintype "output"))
      (node (ref "A24") (pin "E1") (pinfunction "P$2_E1") (pintype "bidirectional"))
    )
    (net (code "15") (name "0ENABLE_L") (class "Default")
      (node (ref "A14") (pin "H1") (pinfunction "C_H1") (pintype "input"))
      (node (ref "C4") (pin "+") (pinfunction "+_+") (pintype "passive"))
      (node (ref "C5") (pin "+") (pinfunction "+_+") (pintype "passive"))
      (node (ref "R8") (pin "1") (pinfunction "1_1") (pintype "passive"))
    )
    (net (code "16") (name "0EOTFF_L") (class "Default")
      (node (ref "A04") (pin "D2") (pinfunction "A_D2") (pintype "input"))
      (node (ref "A11") (pin "F1") (pinfunction "OUT_F1") (pintype "output"))
      (node (ref "A11") (pin "U2") (pinfunction "IN2_U2") (pintype "input"))
    )
    (net (code "17") (name "0EOT_L") (class "Default")
      (node (ref "A11") (pin "T2") (pinfunction "IN1_T2") (pintype "input"))
      (node (ref "B24") (pin "D2") (pinfunction "P$2_D2") (pintype "bidirectional"))
    )
    (net (code "18") (name "0FILEGAP_L") (class "Default")
      (node (ref "A12") (pin "S1") (pinfunction "OUT_S1") (pintype "output"))
      (node (ref "A24") (pin "J1") (pinfunction "P$2_J1") (pintype "bidirectional"))
    )
    (net (code "19") (name "0FILE_PROT_L") (class "Default")
      (node (ref "A04") (pin "M1") (pinfunction "A_M1") (pintype "input"))
      (node (ref "B24") (pin "L1") (pinfunction "P$2_L1") (pintype "bidirectional"))
    )
    (net (code "20") (name "0FWD_ENABLE") (class "Default")
      (node (ref "A11") (pin "M2") (pinfunction "IN2_M2") (pintype "input"))
      (node (ref "A11") (pin "S2") (pinfunction "OUT_S2") (pintype "output"))
      (node (ref "A15") (pin "A1") (pinfunction "IN1_A1") (pintype "input"))
      (node (ref "A17") (pin "J2") (pinfunction "IN2_J2") (pintype "input"))
    )
    (net (code "21") (name "0FWD_LD_L") (class "Default")
      (node (ref "A09") (pin "F2") (pinfunction "IN3_F2") (pintype "input"))
      (node (ref "A09") (pin "U1") (pinfunction "OUT_U1") (pintype "output"))
      (node (ref "A12") (pin "L2") (pinfunction "IN2_L2") (pintype "input"))
    )
    (net (code "22") (name "0GAPSP_L") (class "Default")
      (node (ref "A11") (pin "E2") (pinfunction "IN2_E2") (pintype "input"))
      (node (ref "A14") (pin "B1") (pinfunction "C_B1") (pintype "input"))
      (node (ref "A14") (pin "D2") (pinfunction "C_D2") (pintype "input"))
      (node (ref "A16") (pin "L2") (pinfunction "OUT_L2") (pintype "output"))
    )
    (net (code "23") (name "0GAP_H") (class "Default")
      (node (ref "A13") (pin "F2") (pinfunction "F2_F2") (pintype "output"))
      (node (ref "A14") (pin "L2") (pinfunction "C_L2") (pintype "input"))
      (node (ref "A14") (pin "N1") (pinfunction "C_N1") (pintype "input"))
      (node (ref "A17") (pin "H1") (pinfunction "IN1_H1") (pintype "input"))
    )
    (net (code "24") (name "0GAP_L") (class "Default")
      (node (ref "A09") (pin "R1") (pinfunction "IN2_R1") (pintype "input"))
      (node (ref "A13") (pin "H2") (pinfunction "H2_H2") (pintype "output"))
      (node (ref "A13") (pin "L1") (pinfunction "M1_L1") (pintype "input"))
    )
    (net (code "25") (name "0GIP_L") (class "Default")
      (node (ref "A04") (pin "H1") (pinfunction "B_H1") (pintype "input"))
      (node (ref "A12") (pin "M2") (pinfunction "IN3_M2") (pintype "input"))
      (node (ref "B24") (pin "P2") (pinfunction "P$2_P2") (pintype "bidirectional"))
    )
    (net (code "26") (name "0INITA_L") (class "Default")
      (node (ref "A08") (pin "F2") (pinfunction "OUT_F2") (pintype "output"))
      (node (ref "A09") (pin "S1") (pinfunction "IN3_S1") (pintype "input"))
      (node (ref "A14") (pin "K2") (pinfunction "R_K2") (pintype "input"))
    )
    (net (code "27") (name "0INITB_L") (class "Default")
      (node (ref "A08") (pin "U1") (pinfunction "OUT_U1") (pintype "output"))
      (node (ref "A14") (pin "A1") (pinfunction "R_A1") (pintype "input"))
    )
    (net (code "28") (name "0IOT01L") (class "Default")
      (node (ref "A15") (pin "V1") (pinfunction "OUT_V1") (pintype "output"))
      (node (ref "A16") (pin "N1") (pinfunction "IN_N1") (pintype "input"))
      (node (ref "A17") (pin "E1") (pinfunction "IN2_E1") (pintype "input"))
    )
    (net (code "29") (name "0IOT02L") (class "Default")
      (node (ref "A04") (pin "C1") (pinfunction "C_C1") (pintype "input"))
      (node (ref "A04") (pin "F2") (pinfunction "C_F2") (pintype "input"))
      (node (ref "A04") (pin "J1") (pinfunction "C_J1") (pintype "input"))
      (node (ref "A04") (pin "M2") (pinfunction "C_M2") (pintype "input"))
      (node (ref "A04") (pin "P1") (pinfunction "C_P1") (pintype "input"))
      (node (ref "A09") (pin "J1") (pinfunction "OUT_J1") (pintype "output"))
    )
    (net (code "30") (name "0IOT03_1L") (class "Default")
      (node (ref "A08") (pin "H2") (pinfunction "IN_H2") (pintype "input"))
      (node (ref "A09") (pin "N1") (pinfunction "OUT_N1") (pintype "output"))
      (node (ref "A11") (pin "J2") (pinfunction "IN2_J2") (pintype "input"))
    )
    (net (code "31") (name "0IOT04L") (class "Default")
      (node (ref "A08") (pin "U2") (pinfunction "IN_U2") (pintype "input"))
      (node (ref "A09") (pin "S2") (pinfunction "OUT_S2") (pintype "output"))
      (node (ref "A11") (pin "R1") (pinfunction "IN2_R1") (pintype "input"))
    )
    (net (code "32") (name "0IOT05_1L") (class "Default")
      (node (ref "A16") (pin "D1") (pinfunction "IN_D1") (pintype "input"))
      (node (ref "A17") (pin "U2") (pinfunction "IN2_U2") (pintype "input"))
      (node (ref "A18") (pin "V2") (pinfunction "OUT_V2") (pintype "output"))
    )
    (net (code "33") (name "0IOT06_2L") (class "Default")
      (node (ref "A09") (pin "M2") (pinfunction "OUT_M2") (pintype "output"))
      (node (ref "A24") (pin "L1") (pinfunction "P$2_L1") (pintype "bidirectional"))
    )
    (net (code "34") (name "0IOT07_1L") (class "Default")
      (node (ref "A05") (pin "A1") (pinfunction "A_A1") (pintype "input"))
      (node (ref "A15") (pin "M2") (pinfunction "OUT_M2") (pintype "output"))
    )
    (net (code "35") (name "0IOT07_2L") (class "Default")
      (node (ref "A05") (pin "F2") (pinfunction "C_F2") (pintype "input"))
      (node (ref "A05") (pin "J1") (pinfunction "C_J1") (pintype "input"))
      (node (ref "A05") (pin "M2") (pinfunction "C_M2") (pintype "input"))
      (node (ref "A05") (pin "P1") (pinfunction "C_P1") (pintype "input"))
      (node (ref "A05") (pin "T2") (pinfunction "C_T2") (pintype "input"))
      (node (ref "A15") (pin "U1") (pinfunction "OUT_U1") (pintype "output"))
    )
    (net (code "36") (name "0IRG_H") (class "Default")
      (node (ref "A08") (pin "R1") (pinfunction "IN_R1") (pintype "input"))
      (node (ref "A11") (pin "F2") (pinfunction "OUT_F2") (pintype "output"))
    )
    (net (code "37") (name "0IRG_L") (class "Default")
      (node (ref "A08") (pin "S1") (pinfunction "OUT_S1") (pintype "output"))
      (node (ref "A13") (pin "L2") (pinfunction "S1_L2") (pintype "input"))
      (node (ref "A15") (pin "M1") (pinfunction "IN3_M1") (pintype "input"))
      (node (ref "A24") (pin "H1") (pinfunction "P$2_H1") (pintype "bidirectional"))
    )
    (net (code "38") (name "0LD_FWD_L") (class "Default")
      (node (ref "A11") (pin "N2") (pinfunction "OUT_N2") (pintype "output"))
      (node (ref "A14") (pin "K1") (pinfunction "S_K1") (pintype "input"))
      (node (ref "A24") (pin "B1") (pinfunction "P$2_B1") (pintype "bidirectional"))
    )
    (net (code "39") (name "0LPE_L") (class "Default")
      (node (ref "A05") (pin "F1") (pinfunction "A_F1") (pintype "input"))
      (node (ref "A20") (pin "L1") (pinfunction "EVEN_L1") (pintype "output"))
    )
    (net (code "40") (name "0MB09H") (class "Default")
      (node (ref "A08") (pin "B1") (pinfunction "OUT_B1") (pintype "output"))
      (node (ref "A09") (pin "J2") (pinfunction "IN1_J2") (pintype "input"))
      (node (ref "A15") (pin "J2") (pinfunction "IN1_J2") (pintype "input"))
      (node (ref "A15") (pin "P1") (pinfunction "IN1_P1") (pintype "input"))
      (node (ref "A18") (pin "R2") (pinfunction "IN1_R2") (pintype "input"))
      (node (ref "A18") (pin "S2") (pinfunction "IN2_S2") (pintype "input"))
    )
    (net (code "41") (name "0MB09L") (class "Default")
      (node (ref "A07") (pin "N2") (pinfunction "OUT_N2") (pintype "output"))
      (node (ref "A08") (pin "A1") (pinfunction "IN_A1") (pintype "input"))
      (node (ref "A09") (pin "E1") (pinfunction "IN1_E1") (pintype "input"))
      (node (ref "A09") (pin "K1") (pinfunction "IN1_K1") (pintype "input"))
      (node (ref "A15") (pin "T2") (pinfunction "IN1_T2") (pintype "input"))
    )
    (net (code "42") (name "0MB10H") (class "Default")
      (node (ref "A08") (pin "D2") (pinfunction "OUT_D2") (pintype "output"))
      (node (ref "A09") (pin "L1") (pinfunction "IN2_L1") (pintype "input"))
      (node (ref "A15") (pin "K2") (pinfunction "IN2_K2") (pintype "input"))
    )
    (net (code "43") (name "0MB10L") (class "Default")
      (node (ref "A07") (pin "R2") (pinfunction "OUT_R2") (pintype "output"))
      (node (ref "A08") (pin "C1") (pinfunction "IN_C1") (pintype "input"))
      (node (ref "A09") (pin "N2") (pinfunction "IN1_N2") (pintype "input"))
      (node (ref "A15") (pin "U2") (pinfunction "IN2_U2") (pintype "input"))
      (node (ref "A18") (pin "T2") (pinfunction "IN3_T2") (pintype "input"))
    )
    (net (code "44") (name "0MB11H") (class "Default")
      (node (ref "A08") (pin "E1") (pinfunction "OUT_E1") (pintype "output"))
      (node (ref "A15") (pin "R1") (pinfunction "IN2_R1") (pintype "input"))
    )
    (net (code "45") (name "0MB11L") (class "Default")
      (node (ref "A07") (pin "T2") (pinfunction "OUT_T2") (pintype "output"))
      (node (ref "A08") (pin "D1") (pinfunction "IN_D1") (pintype "input"))
      (node (ref "A09") (pin "F1") (pinfunction "IN2_F1") (pintype "input"))
      (node (ref "A09") (pin "K2") (pinfunction "IN2_K2") (pintype "input"))
      (node (ref "A09") (pin "P2") (pinfunction "IN2_P2") (pintype "input"))
    )
    (net (code "46") (name "0MYOP1") (class "Default")
      (node (ref "A06") (pin "A1") (pinfunction "A1_A1") (pintype "output"))
      (node (ref "A09") (pin "M1") (pinfunction "IN3_M1") (pintype "input"))
      (node (ref "A15") (pin "L2") (pinfunction "IN3_L2") (pintype "input"))
      (node (ref "A15") (pin "V2") (pinfunction "IN3_V2") (pintype "input"))
      (node (ref "A18") (pin "U2") (pinfunction "IN4_U2") (pintype "input"))
    )
    (net (code "47") (name "0MYOP2") (class "Default")
      (node (ref "A06") (pin "C1") (pinfunction "C1_C1") (pintype "output"))
      (node (ref "A09") (pin "H1") (pinfunction "IN3_H1") (pintype "input"))
      (node (ref "A09") (pin "L2") (pinfunction "IN3_L2") (pintype "input"))
      (node (ref "A15") (pin "S1") (pinfunction "IN3_S1") (pintype "input"))
    )
    (net (code "48") (name "0MYOP4") (class "Default")
      (node (ref "A06") (pin "E1") (pinfunction "E1_E1") (pintype "output"))
      (node (ref "A09") (pin "R2") (pinfunction "IN3_R2") (pintype "input"))
    )
    (net (code "49") (name "0RD00H") (class "Default")
      (node (ref "A21") (pin "E1") (pinfunction "1A_E1") (pintype "input"))
      (node (ref "A22") (pin "B1") (pinfunction "OUT_B1") (pintype "output"))
      (node (ref "A22") (pin "C1") (pinfunction "IN_C1") (pintype "input"))
    )
    (net (code "50") (name "0RD00L") (class "Default")
      (node (ref "A05") (pin "M1") (pinfunction "A_M1") (pintype "input"))
      (node (ref "A21") (pin "A1") (pinfunction "1B_A1") (pintype "input"))
      (node (ref "A22") (pin "D2") (pinfunction "OUT_D2") (pintype "output"))
    )
    (net (code "51") (name "0RD01H") (class "Default")
      (node (ref "A21") (pin "F1") (pinfunction "2A_F1") (pintype "input"))
      (node (ref "A22") (pin "E1") (pinfunction "OUT_E1") (pintype "output"))
      (node (ref "A22") (pin "F1") (pinfunction "IN_F1") (pintype "input"))
    )
    (net (code "52") (name "0RD01L") (class "Default")
      (node (ref "A05") (pin "N1") (pinfunction "B_N1") (pintype "input"))
      (node (ref "A21") (pin "B1") (pinfunction "2B_B1") (pintype "input"))
      (node (ref "A22") (pin "H1") (pinfunction "OUT_H1") (pintype "output"))
    )
    (net (code "53") (name "0RD02H") (class "Default")
      (node (ref "A21") (pin "H1") (pinfunction "4A_H1") (pintype "input"))
      (node (ref "A22") (pin "K1") (pinfunction "OUT_K1") (pintype "output"))
      (node (ref "A22") (pin "L1") (pinfunction "IN_L1") (pintype "input"))
    )
    (net (code "54") (name "0RD02L") (class "Default")
      (node (ref "A05") (pin "D2") (pinfunction "A_D2") (pintype "input"))
      (node (ref "A21") (pin "C1") (pinfunction "4B_C1") (pintype "input"))
      (node (ref "A22") (pin "M1") (pinfunction "OUT_M1") (pintype "output"))
    )
    (net (code "55") (name "0RD03H") (class "Default")
      (node (ref "A21") (pin "J1") (pinfunction "8A_J1") (pintype "input"))
      (node (ref "A22") (pin "P1") (pinfunction "OUT_P1") (pintype "output"))
      (node (ref "A22") (pin "R1") (pinfunction "IN_R1") (pintype "input"))
    )
    (net (code "56") (name "0RD03L") (class "Default")
      (node (ref "A05") (pin "E2") (pinfunction "B_E2") (pintype "input"))
      (node (ref "A21") (pin "D1") (pinfunction "8B_D1") (pintype "input"))
      (node (ref "A22") (pin "S1") (pinfunction "OUT_S1") (pintype "output"))
    )
    (net (code "57") (name "0RD04H") (class "Default")
      (node (ref "A21") (pin "P2") (pinfunction "1A_P2") (pintype "input"))
      (node (ref "A22") (pin "E2") (pinfunction "IN_E2") (pintype "input"))
      (node (ref "A22") (pin "U1") (pinfunction "OUT_U1") (pintype "output"))
    )
    (net (code "58") (name "0RD04L") (class "Default")
      (node (ref "A05") (pin "K2") (pinfunction "A_K2") (pintype "input"))
      (node (ref "A21") (pin "K2") (pinfunction "1B_K2") (pintype "input"))
      (node (ref "A22") (pin "F2") (pinfunction "OUT_F2") (pintype "output"))
    )
    (net (code "59") (name "0RD05H") (class "Default")
      (node (ref "A21") (pin "R2") (pinfunction "2A_R2") (pintype "input"))
      (node (ref "A22") (pin "J2") (pinfunction "OUT_J2") (pintype "output"))
      (node (ref "A22") (pin "K2") (pinfunction "IN_K2") (pintype "input"))
    )
    (net (code "60") (name "0RD05L") (class "Default")
      (node (ref "A05") (pin "L2") (pinfunction "B_L2") (pintype "input"))
      (node (ref "A21") (pin "L2") (pinfunction "2B_L2") (pintype "input"))
      (node (ref "A22") (pin "L2") (pinfunction "OUT_L2") (pintype "output"))
    )
    (net (code "61") (name "0RD06H") (class "Default")
      (node (ref "A21") (pin "S2") (pinfunction "4A_S2") (pintype "input"))
      (node (ref "A22") (pin "N2") (pinfunction "OUT_N2") (pintype "output"))
      (node (ref "A22") (pin "P2") (pinfunction "IN_P2") (pintype "input"))
    )
    (net (code "62") (name "0RD06L") (class "Default")
      (node (ref "A05") (pin "R2") (pinfunction "A_R2") (pintype "input"))
      (node (ref "A21") (pin "M2") (pinfunction "4B_M2") (pintype "input"))
      (node (ref "A22") (pin "R2") (pinfunction "OUT_R2") (pintype "output"))
    )
    (net (code "63") (name "0RD07H") (class "Default")
      (node (ref "A21") (pin "T2") (pinfunction "8A_T2") (pintype "input"))
      (node (ref "A22") (pin "T2") (pinfunction "OUT_T2") (pintype "output"))
      (node (ref "A22") (pin "U2") (pinfunction "IN_U2") (pintype "input"))
    )
    (net (code "64") (name "0RD07L") (class "Default")
      (node (ref "A05") (pin "S2") (pinfunction "B_S2") (pintype "input"))
      (node (ref "A21") (pin "N2") (pinfunction "8B_N2") (pintype "input"))
      (node (ref "A22") (pin "V2") (pinfunction "OUT_V2") (pintype "output"))
    )
    (net (code "65") (name "0RD_DATA00L") (class "Default")
      (node (ref "A22") (pin "A1") (pinfunction "IN_A1") (pintype "input"))
      (node (ref "B24") (pin "P1") (pinfunction "P$2_P1") (pintype "bidirectional"))
    )
    (net (code "66") (name "0RD_DATA01L") (class "Default")
      (node (ref "A22") (pin "D1") (pinfunction "IN_D1") (pintype "input"))
      (node (ref "B24") (pin "S1") (pinfunction "P$2_S1") (pintype "bidirectional"))
    )
    (net (code "67") (name "0RD_DATA02L") (class "Default")
      (node (ref "A22") (pin "J1") (pinfunction "IN_J1") (pintype "input"))
      (node (ref "B24") (pin "U1") (pinfunction "P$2_U1") (pintype "bidirectional"))
    )
    (net (code "68") (name "0RD_DATA03L") (class "Default")
      (node (ref "A22") (pin "N1") (pinfunction "IN_N1") (pintype "input"))
      (node (ref "B24") (pin "V1") (pinfunction "P$2_V1") (pintype "bidirectional"))
    )
    (net (code "69") (name "0RD_DATA04L") (class "Default")
      (node (ref "A22") (pin "V1") (pinfunction "IN_V1") (pintype "input"))
      (node (ref "B24") (pin "T2") (pinfunction "P$2_T2") (pintype "bidirectional"))
    )
    (net (code "70") (name "0RD_DATA05L") (class "Default")
      (node (ref "A22") (pin "H2") (pinfunction "IN_H2") (pintype "input"))
      (node (ref "B24") (pin "V2") (pinfunction "P$2_V2") (pintype "bidirectional"))
    )
    (net (code "71") (name "0RD_DATA06L") (class "Default")
      (node (ref "A22") (pin "M2") (pinfunction "IN_M2") (pintype "input"))
      (node (ref "B24") (pin "B1") (pinfunction "P$2_B1") (pintype "bidirectional"))
    )
    (net (code "72") (name "0RD_DATA07L") (class "Default")
      (node (ref "A22") (pin "S2") (pinfunction "IN_S2") (pintype "input"))
      (node (ref "B24") (pin "D1") (pinfunction "P$2_D1") (pintype "bidirectional"))
    )
    (net (code "73") (name "0RD_ENABLE_L") (class "Default")
      (node (ref "A10") (pin "E2") (pinfunction "D_E2") (pintype "input"))
      (node (ref "A15") (pin "S2") (pinfunction "OUT_S2") (pintype "output"))
    )
    (net (code "74") (name "0RD_FWD_F_H") (class "Default")
      (node (ref "A15") (pin "R2") (pinfunction "IN3_R2") (pintype "input"))
    )
    (net (code "75") (name "0RD_FWD_L") (class "Default")
      (node (ref "A14") (pin "N2") (pinfunction "S_N2") (pintype "input"))
      (node (ref "A18") (pin "F2") (pinfunction "IN3_F2") (pintype "input"))
      (node (ref "A18") (pin "P2") (pinfunction "OUT_P2") (pintype "output"))
    )
    (net (code "76") (name "0RD_LD_L") (class "Default")
      (node (ref "A09") (pin "D2") (pinfunction "IN1_D2") (pintype "input"))
      (node (ref "A18") (pin "D2") (pinfunction "IN1_D2") (pintype "input"))
      (node (ref "A18") (pin "E2") (pinfunction "IN2_E2") (pintype "input"))
      (node (ref "A18") (pin "L1") (pinfunction "OUT_L1") (pintype "output"))
    )
    (net (code "77") (name "0RD_PARITY_L") (class "Default")
      (node (ref "A16") (pin "E2") (pinfunction "IN_E2") (pintype "input"))
      (node (ref "B24") (pin "E1") (pinfunction "P$2_E1") (pintype "bidirectional"))
    )
    (net (code "78") (name "0RD_P_H") (class "Default")
      (node (ref "A16") (pin "C1") (pinfunction "IN_C1") (pintype "input"))
      (node (ref "A16") (pin "F2") (pinfunction "OUT_F2") (pintype "output"))
      (node (ref "A20") (pin "B1") (pinfunction "2B_B1") (pintype "input"))
      (node (ref "A20") (pin "F1") (pinfunction "2A_F1") (pintype "input"))
    )
    (net (code "79") (name "0RD_P_L") (class "Default")
      (node (ref "A16") (pin "D2") (pinfunction "OUT_D2") (pintype "output"))
    )
    (net (code "80") (name "0RD_REV_L") (class "Default")
      (node (ref "A14") (pin "R1") (pinfunction "S_R1") (pintype "input"))
      (node (ref "A18") (pin "H2") (pinfunction "IN4_H2") (pintype "input"))
      (node (ref "A18") (pin "S1") (pinfunction "OUT_S1") (pintype "output"))
    )
    (net (code "81") (name "0READY") (class "Default")
      (node (ref "A04") (pin "K2") (pinfunction "A_K2") (pintype "input"))
    )
    (net (code "82") (name "0READ_WRITE_H") (class "Default")
      (node (ref "A04") (pin "E2") (pinfunction "B_E2") (pintype "input"))
      (node (ref "A10") (pin "M2") (pinfunction "D_M2") (pintype "input"))
      (node (ref "A10") (pin "T2") (pinfunction "D_T2") (pintype "input"))
      (node (ref "A14") (pin "H2") (pinfunction "1_H2") (pintype "output"))
      (node (ref "A17") (pin "E2") (pinfunction "IN2_E2") (pintype "input"))
      (node (ref "A24") (pin "T2") (pinfunction "P$2_T2") (pintype "bidirectional"))
    )
    (net (code "83") (name "0RESET_L") (class "Default")
      (node (ref "A08") (pin "T2") (pinfunction "OUT_T2") (pintype "output"))
      (node (ref "A11") (pin "E1") (pinfunction "IN2_E1") (pintype "input"))
      (node (ref "A11") (pin "M1") (pinfunction "IN2_M1") (pintype "input"))
      (node (ref "A14") (pin "S2") (pinfunction "C_S2") (pintype "input"))
      (node (ref "A17") (pin "M1") (pinfunction "IN2_M1") (pintype "input"))
      (node (ref "A17") (pin "R2") (pinfunction "IN2_R2") (pintype "input"))
    )
    (net (code "84") (name "0REV_ENABLE") (class "Default")
      (node (ref "A15") (pin "F2") (pinfunction "IN3_F2") (pintype "input"))
      (node (ref "A17") (pin "N2") (pinfunction "OUT_N2") (pintype "output"))
    )
    (net (code "85") (name "0REWIND_L") (class "Default")
      (node (ref "A11") (pin "A1") (pinfunction "IN1_A1") (pintype "input"))
      (node (ref "A12") (pin "E1") (pinfunction "OUT_E1") (pintype "output"))
      (node (ref "A24") (pin "D1") (pinfunction "P$2_D1") (pintype "bidirectional"))
    )
    (net (code "86") (name "0RWND_DONE_L") (class "Default")
      (node (ref "A12") (pin "P2") (pinfunction "OUT_P2") (pintype "output"))
      (node (ref "A12") (pin "R2") (pinfunction "IN1_R2") (pintype "input"))
      (node (ref "A12") (pin "S2") (pinfunction "IN2_S2") (pintype "input"))
      (node (ref "A12") (pin "T2") (pinfunction "IN3_T2") (pintype "input"))
    )
    (net (code "87") (name "0R_RESET_L") (class "Default")
      (node (ref "A06") (pin "K1") (pinfunction "OUT_K1") (pintype "output"))
      (node (ref "A11") (pin "B1") (pinfunction "IN2_B1") (pintype "input"))
      (node (ref "A11") (pin "P1") (pinfunction "IN1_P1") (pintype "input"))
      (node (ref "A24") (pin "K2") (pinfunction "P$2_K2") (pintype "bidirectional"))
    )
    (net (code "88") (name "0STROBE_H") (class "Default")
      (node (ref "A10") (pin "D2") (pinfunction "C_D2") (pintype "input"))
      (node (ref "A16") (pin "B1") (pinfunction "OUT_B1") (pintype "output"))
    )
    (net (code "89") (name "0STROBE_L") (class "Default")
      (node (ref "A13") (pin "S1") (pinfunction "S1_S1") (pintype "input"))
      (node (ref "A13") (pin "U1") (pinfunction "U1_U1") (pintype "input"))
      (node (ref "A16") (pin "A1") (pinfunction "IN_A1") (pintype "input"))
      (node (ref "B24") (pin "H1") (pinfunction "P$2_H1") (pintype "bidirectional"))
    )
    (net (code "90") (name "00SYNC_FWD_H") (class "Default")
      (node (ref "A14") (pin "P2") (pinfunction "1_P2") (pintype "output"))
      (node (ref "A15") (pin "B1") (pinfunction "IN2_B1") (pintype "input"))
    )
    (net (code "91") (name "0SYNC_FWD_L") (class "Default")
      (node (ref "A15") (pin "D1") (pinfunction "OUT_D1") (pintype "output"))
      (node (ref "A15") (pin "L1") (pinfunction "IN2_L1") (pintype "input"))
      (node (ref "A19") (pin "M2") (pinfunction "H2_M2") (pintype "input"))
      (node (ref "A19") (pin "N2") (pinfunction "J2_N2") (pintype "input"))
      (node (ref "A24") (pin "P2") (pinfunction "P$2_P2") (pintype "bidirectional"))
    )
    (net (code "92") (name "00SYNC_REV_H") (class "Default")
      (node (ref "A14") (pin "S1") (pinfunction "1_S1") (pintype "output"))
      (node (ref "A15") (pin "E2") (pinfunction "IN2_E2") (pintype "input"))
    )
    (net (code "93") (name "0SYNC_REV_L") (class "Default")
      (node (ref "A15") (pin "F1") (pinfunction "IN2_F1") (pintype "input"))
      (node (ref "A15") (pin "H2") (pinfunction "OUT_H2") (pintype "output"))
      (node (ref "A19") (pin "P2") (pinfunction "K2_P2") (pintype "input"))
      (node (ref "A24") (pin "S2") (pinfunction "P$2_S2") (pintype "bidirectional"))
    )
    (net (code "94") (name "0TM_L") (class "Default")
      (node (ref "A04") (pin "F1") (pinfunction "A_F1") (pintype "input"))
      (node (ref "B24") (pin "H2") (pinfunction "P$2_H2") (pintype "bidirectional"))
    )
    (net (code "95") (name "0TR_READY_H") (class "Default")
      (node (ref "A08") (pin "P1") (pinfunction "OUT_P1") (pintype "output"))
      (node (ref "A17") (pin "J1") (pinfunction "IN2_J1") (pintype "input"))
    )
    (net (code "96") (name "0TR_READY_L") (class "Default")
      (node (ref "A04") (pin "A1") (pinfunction "A_A1") (pintype "input"))
      (node (ref "A08") (pin "N1") (pinfunction "IN_N1") (pintype "input"))
      (node (ref "A12") (pin "U2") (pinfunction "IN4_U2") (pintype "input"))
      (node (ref "B24") (pin "K2") (pinfunction "P$2_K2") (pintype "bidirectional"))
    )
    (net (code "97") (name "0WDATA00L") (class "Default")
      (node (ref "A07") (pin "K1") (pinfunction "OUT_K1") (pintype "output"))
      (node (ref "A24") (pin "M1") (pinfunction "P$2_M1") (pintype "bidirectional"))
    )
    (net (code "98") (name "0WDATA01L") (class "Default")
      (node (ref "A07") (pin "M1") (pinfunction "OUT_M1") (pintype "output"))
      (node (ref "A24") (pin "P1") (pinfunction "P$2_P1") (pintype "bidirectional"))
    )
    (net (code "99") (name "0WDATA02L") (class "Default")
      (node (ref "A07") (pin "P1") (pinfunction "OUT_P1") (pintype "output"))
      (node (ref "A24") (pin "S1") (pinfunction "P$2_S1") (pintype "bidirectional"))
    )
    (net (code "100") (name "0WDATA03L") (class "Default")
      (node (ref "A07") (pin "S1") (pinfunction "OUT_S1") (pintype "output"))
      (node (ref "A24") (pin "U1") (pinfunction "P$2_U1") (pintype "bidirectional"))
    )
    (net (code "101") (name "0WDATA04L") (class "Default")
      (node (ref "A07") (pin "U1") (pinfunction "OUT_U1") (pintype "output"))
      (node (ref "A24") (pin "V1") (pinfunction "P$2_V1") (pintype "bidirectional"))
    )
    (net (code "102") (name "0WDATA05L") (class "Default")
      (node (ref "A07") (pin "F2") (pinfunction "OUT_F2") (pintype "output"))
      (node (ref "A24") (pin "D2") (pinfunction "P$2_D2") (pintype "bidirectional"))
    )
    (net (code "103") (name "0WDATA06L") (class "Default")
      (node (ref "A07") (pin "J2") (pinfunction "OUT_J2") (pintype "output"))
      (node (ref "A24") (pin "E2") (pinfunction "P$2_E2") (pintype "bidirectional"))
    )
    (net (code "104") (name "0WDATA07L") (class "Default")
      (node (ref "A07") (pin "L2") (pinfunction "OUT_L2") (pintype "output"))
      (node (ref "A24") (pin "H2") (pinfunction "P$2_H2") (pintype "bidirectional"))
    )
    (net (code "105") (name "0WR_LD_L") (class "Default")
      (node (ref "A09") (pin "E2") (pinfunction "IN2_E2") (pintype "input"))
      (node (ref "A12") (pin "J2") (pinfunction "OUT_J2") (pintype "output"))
    )
    (net (code "106") (name "0WR_SET_H") (class "Default")
      (node (ref "A14") (pin "E1") (pinfunction "1_E1") (pintype "output"))
      (node (ref "A17") (pin "H2") (pinfunction "IN1_H2") (pintype "input"))
    )
    (net (code "107") (name "1AC00H") (class "Default")
      (node (ref "B08") (pin "H1") (pinfunction "OUT_H1") (pintype "output"))
    )
    (net (code "108") (name "1AC00L") (class "Default")
      (node (ref "B07") (pin "B1") (pinfunction "OUT_B1") (pintype "output"))
      (node (ref "B08") (pin "F1") (pinfunction "IN_F1") (pintype "input"))
    )
    (net (code "109") (name "1AC01H") (class "Default")
      (node (ref "B08") (pin "K1") (pinfunction "OUT_K1") (pintype "output"))
    )
    (net (code "110") (name "1AC01L") (class "Default")
      (node (ref "B07") (pin "E1") (pinfunction "OUT_E1") (pintype "output"))
      (node (ref "B08") (pin "J1") (pinfunction "IN_J1") (pintype "input"))
    )
    (net (code "111") (name "1AC02H") (class "Default")
      (node (ref "B08") (pin "M1") (pinfunction "OUT_M1") (pintype "output"))
    )
    (net (code "112") (name "1AC02L") (class "Default")
      (node (ref "B07") (pin "H1") (pinfunction "OUT_H1") (pintype "output"))
      (node (ref "B08") (pin "L1") (pinfunction "IN_L1") (pintype "input"))
    )
    (net (code "113") (name "1INITA_L") (class "Default")
      (node (ref "B08") (pin "F2") (pinfunction "OUT_F2") (pintype "output"))
    )
    (net (code "114") (name "1INITB_L") (class "Default")
      (node (ref "B08") (pin "U1") (pinfunction "OUT_U1") (pintype "output"))
    )
    (net (code "115") (name "1IOT01L") (class "Default")
      (node (ref "B15") (pin "V1") (pinfunction "OUT_V1") (pintype "output"))
    )
    (net (code "116") (name "1IOT02L") (class "Default")
      (node (ref "B09") (pin "J1") (pinfunction "OUT_J1") (pintype "output"))
    )
    (net (code "117") (name "1IOT03_1L") (class "Default")
      (node (ref "B09") (pin "N1") (pinfunction "OUT_N1") (pintype "output"))
    )
    (net (code "118") (name "1IOT04L") (class "Default")
      (node (ref "B09") (pin "S2") (pinfunction "OUT_S2") (pintype "output"))
      (node (ref "B11") (pin "R1") (pinfunction "IN2_R1") (pintype "input"))
    )
    (net (code "119") (name "1IOT05_1L") (class "Default")
      (node (ref "B18") (pin "V2") (pinfunction "OUT_V2") (pintype "output"))
    )
    (net (code "120") (name "1IOT06_2L") (class "Default")
      (node (ref "A23") (pin "L1") (pinfunction "P$2_L1") (pintype "bidirectional"))
      (node (ref "B09") (pin "M2") (pinfunction "OUT_M2") (pintype "output"))
    )
    (net (code "121") (name "1IOT07_1L") (class "Default")
      (node (ref "B15") (pin "M2") (pinfunction "OUT_M2") (pintype "output"))
    )
    (net (code "122") (name "1IOT07_2L") (class "Default")
      (node (ref "B15") (pin "U1") (pinfunction "OUT_U1") (pintype "output"))
    )
    (net (code "123") (name "1MB09H") (class "Default")
      (node (ref "B08") (pin "B1") (pinfunction "OUT_B1") (pintype "output"))
      (node (ref "B09") (pin "J2") (pinfunction "IN1_J2") (pintype "input"))
      (node (ref "B15") (pin "J2") (pinfunction "IN1_J2") (pintype "input"))
      (node (ref "B15") (pin "P1") (pinfunction "IN1_P1") (pintype "input"))
      (node (ref "B18") (pin "R2") (pinfunction "IN1_R2") (pintype "input"))
      (node (ref "B18") (pin "S2") (pinfunction "IN2_S2") (pintype "input"))
    )
    (net (code "124") (name "1MB09L") (class "Default")
      (node (ref "B07") (pin "N2") (pinfunction "OUT_N2") (pintype "output"))
      (node (ref "B08") (pin "A1") (pinfunction "IN_A1") (pintype "input"))
      (node (ref "B09") (pin "E1") (pinfunction "IN1_E1") (pintype "input"))
      (node (ref "B09") (pin "K1") (pinfunction "IN1_K1") (pintype "input"))
      (node (ref "B15") (pin "T2") (pinfunction "IN1_T2") (pintype "input"))
    )
    (net (code "125") (name "1MB10H") (class "Default")
      (node (ref "B08") (pin "D2") (pinfunction "OUT_D2") (pintype "output"))
      (node (ref "B09") (pin "L1") (pinfunction "IN2_L1") (pintype "input"))
      (node (ref "B15") (pin "K2") (pinfunction "IN2_K2") (pintype "input"))
    )
    (net (code "126") (name "1MB10L") (class "Default")
      (node (ref "B07") (pin "R2") (pinfunction "OUT_R2") (pintype "output"))
      (node (ref "B08") (pin "C1") (pinfunction "IN_C1") (pintype "input"))
      (node (ref "B09") (pin "N2") (pinfunction "IN1_N2") (pintype "input"))
      (node (ref "B15") (pin "U2") (pinfunction "IN2_U2") (pintype "input"))
      (node (ref "B18") (pin "T2") (pinfunction "IN3_T2") (pintype "input"))
    )
    (net (code "127") (name "1MB11H") (class "Default")
      (node (ref "B08") (pin "E1") (pinfunction "OUT_E1") (pintype "output"))
      (node (ref "B15") (pin "R1") (pinfunction "IN2_R1") (pintype "input"))
    )
    (net (code "128") (name "1MB11L") (class "Default")
      (node (ref "B07") (pin "T2") (pinfunction "OUT_T2") (pintype "output"))
      (node (ref "B08") (pin "D1") (pinfunction "IN_D1") (pintype "input"))
      (node (ref "B09") (pin "F1") (pinfunction "IN2_F1") (pintype "input"))
      (node (ref "B09") (pin "K2") (pinfunction "IN2_K2") (pintype "input"))
      (node (ref "B09") (pin "P2") (pinfunction "IN2_P2") (pintype "input"))
    )
    (net (code "129") (name "1MYOP1") (class "Default")
      (node (ref "B06") (pin "A1") (pinfunction "A1_A1") (pintype "output"))
      (node (ref "B09") (pin "M1") (pinfunction "IN3_M1") (pintype "input"))
      (node (ref "B15") (pin "L2") (pinfunction "IN3_L2") (pintype "input"))
      (node (ref "B15") (pin "V2") (pinfunction "IN3_V2") (pintype "input"))
      (node (ref "B18") (pin "U2") (pinfunction "IN4_U2") (pintype "input"))
    )
    (net (code "130") (name "1MYOP2") (class "Default")
      (node (ref "B06") (pin "C1") (pinfunction "C1_C1") (pintype "output"))
      (node (ref "B09") (pin "H1") (pinfunction "IN3_H1") (pintype "input"))
      (node (ref "B09") (pin "L2") (pinfunction "IN3_L2") (pintype "input"))
      (node (ref "B15") (pin "S1") (pinfunction "IN3_S1") (pintype "input"))
    )
    (net (code "131") (name "1MYOP4") (class "Default")
      (node (ref "B06") (pin "E1") (pinfunction "E1_E1") (pintype "output"))
      (node (ref "B09") (pin "R2") (pinfunction "IN3_R2") (pintype "input"))
    )
    (net (code "132") (name "1RESET_L") (class "Default")
      (node (ref "B08") (pin "T2") (pinfunction "OUT_T2") (pintype "output"))
    )
    (net (code "133") (name "1REWIND_L") (class "Default")
      (node (ref "B11") (pin "A1") (pinfunction "IN1_A1") (pintype "input"))
    )
    (net (code "134") (name "1R_RESET_L") (class "Default")
      (node (ref "A23") (pin "K2") (pinfunction "P$2_K2") (pintype "bidirectional"))
      (node (ref "B06") (pin "K1") (pinfunction "OUT_K1") (pintype "output"))
      (node (ref "B11") (pin "B1") (pinfunction "IN2_B1") (pintype "input"))
      (node (ref "B11") (pin "P1") (pinfunction "IN1_P1") (pintype "input"))
    )
    (net (code "135") (name "1WDATA00L") (class "Default")
      (node (ref "A23") (pin "M1") (pinfunction "P$2_M1") (pintype "bidirectional"))
      (node (ref "B07") (pin "K1") (pinfunction "OUT_K1") (pintype "output"))
    )
    (net (code "136") (name "1WDATA01L") (class "Default")
      (node (ref "A23") (pin "P1") (pinfunction "P$2_P1") (pintype "bidirectional"))
      (node (ref "B07") (pin "M1") (pinfunction "OUT_M1") (pintype "output"))
    )
    (net (code "137") (name "1WDATA02L") (class "Default")
      (node (ref "A23") (pin "S1") (pinfunction "P$2_S1") (pintype "bidirectional"))
      (node (ref "B07") (pin "P1") (pinfunction "OUT_P1") (pintype "output"))
    )
    (net (code "138") (name "1WDATA03L") (class "Default")
      (node (ref "A23") (pin "U1") (pinfunction "P$2_U1") (pintype "bidirectional"))
      (node (ref "B07") (pin "S1") (pinfunction "OUT_S1") (pintype "output"))
    )
    (net (code "139") (name "1WDATA04L") (class "Default")
      (node (ref "A23") (pin "V1") (pinfunction "P$2_V1") (pintype "bidirectional"))
      (node (ref "B07") (pin "U1") (pinfunction "OUT_U1") (pintype "output"))
    )
    (net (code "140") (name "1WDATA05L") (class "Default")
      (node (ref "A23") (pin "D2") (pinfunction "P$2_D2") (pintype "bidirectional"))
      (node (ref "B07") (pin "F2") (pinfunction "OUT_F2") (pintype "output"))
    )
    (net (code "141") (name "1WDATA06L") (class "Default")
      (node (ref "A23") (pin "E2") (pinfunction "P$2_E2") (pintype "bidirectional"))
      (node (ref "B07") (pin "J2") (pinfunction "OUT_J2") (pintype "output"))
    )
    (net (code "142") (name "1WDATA07L") (class "Default")
      (node (ref "A23") (pin "H2") (pinfunction "P$2_H2") (pintype "bidirectional"))
      (node (ref "B07") (pin "L2") (pinfunction "OUT_L2") (pintype "output"))
    )
    (net (code "143") (name "A06V1") (class "Default")
      (node (ref "A06") (pin "J1") (pinfunction "IN2_J1") (pintype "input"))
      (node (ref "A06") (pin "L2") (pinfunction "L2_L2") (pintype "input"))
      (node (ref "A06") (pin "N2") (pinfunction "N2_N2") (pintype "input"))
      (node (ref "A06") (pin "U2") (pinfunction "U2_U2") (pintype "input"))
      (node (ref "A06") (pin "V1") (pinfunction "P$1_V1") (pintype "passive"))
    )
    (net (code "144") (name "A11U1") (class "Default")
      (node (ref "A10") (pin "A1") (pinfunction "R_A1") (pintype "input"))
      (node (ref "A10") (pin "K2") (pinfunction "R_K2") (pintype "input"))
      (node (ref "A11") (pin "U1") (pinfunction "P$1_U1") (pintype "passive"))
    )
    (net (code "145") (name "A13R1") (class "Default")
      (node (ref "A13") (pin "J2") (pinfunction "N1_J2") (pintype "input"))
      (node (ref "A13") (pin "M1") (pinfunction "M1_M1") (pintype "input"))
      (node (ref "A13") (pin "R1") (pinfunction "P$1_R1") (pintype "passive"))
    )
    (net (code "146") (name "AC00L") (class "Default")
      (node (ref "A03") (pin "B1") (pinfunction "P$2_B1") (pintype "bidirectional"))
      (node (ref "A04") (pin "D1") (pinfunction "D_D1") (pintype "open_collector"))
      (node (ref "A05") (pin "K1") (pinfunction "D_K1") (pintype "open_collector"))
      (node (ref "B03") (pin "B1") (pinfunction "P$2_B1") (pintype "bidirectional"))
    )
    (net (code "147") (name "AC01L") (class "Default")
      (node (ref "A03") (pin "D1") (pinfunction "P$2_D1") (pintype "bidirectional"))
      (node (ref "A04") (pin "E1") (pinfunction "E_E1") (pintype "open_collector"))
      (node (ref "B03") (pin "D1") (pinfunction "P$2_D1") (pintype "bidirectional"))
    )
    (net (code "148") (name "AC02L") (class "Default")
      (node (ref "A03") (pin "E1") (pinfunction "P$2_E1") (pintype "bidirectional"))
      (node (ref "A04") (pin "K1") (pinfunction "D_K1") (pintype "open_collector"))
      (node (ref "B03") (pin "E1") (pinfunction "P$2_E1") (pintype "bidirectional"))
    )
    (net (code "149") (name "AC03L") (class "Default")
      (node (ref "A03") (pin "H1") (pinfunction "P$2_H1") (pintype "bidirectional"))
      (node (ref "A04") (pin "L1") (pinfunction "E_L1") (pintype "open_collector"))
      (node (ref "B03") (pin "H1") (pinfunction "P$2_H1") (pintype "bidirectional"))
    )
    (net (code "150") (name "AC04L") (class "Default")
      (node (ref "A03") (pin "J1") (pinfunction "P$2_J1") (pintype "bidirectional"))
      (node (ref "A04") (pin "R1") (pinfunction "D_R1") (pintype "open_collector"))
      (node (ref "A05") (pin "R1") (pinfunction "D_R1") (pintype "open_collector"))
      (node (ref "B03") (pin "J1") (pinfunction "P$2_J1") (pintype "bidirectional"))
    )
    (net (code "151") (name "AC05L") (class "Default")
      (node (ref "A03") (pin "L1") (pinfunction "P$2_L1") (pintype "bidirectional"))
      (node (ref "A04") (pin "S1") (pinfunction "E_S1") (pintype "open_collector"))
      (node (ref "A05") (pin "S1") (pinfunction "E_S1") (pintype "open_collector"))
      (node (ref "B03") (pin "L1") (pinfunction "P$2_L1") (pintype "bidirectional"))
    )
    (net (code "152") (name "AC06L") (class "Default")
      (node (ref "A03") (pin "M1") (pinfunction "P$2_M1") (pintype "bidirectional"))
      (node (ref "A04") (pin "H2") (pinfunction "D_H2") (pintype "open_collector"))
      (node (ref "A05") (pin "H2") (pinfunction "D_H2") (pintype "open_collector"))
      (node (ref "B03") (pin "M1") (pinfunction "P$2_M1") (pintype "bidirectional"))
    )
    (net (code "153") (name "AC07L") (class "Default")
      (node (ref "A03") (pin "P1") (pinfunction "P$2_P1") (pintype "bidirectional"))
      (node (ref "A04") (pin "J2") (pinfunction "E_J2") (pintype "open_collector"))
      (node (ref "A05") (pin "J2") (pinfunction "E_J2") (pintype "open_collector"))
      (node (ref "B03") (pin "P1") (pinfunction "P$2_P1") (pintype "bidirectional"))
    )
    (net (code "154") (name "AC08L") (class "Default")
      (node (ref "A03") (pin "S1") (pinfunction "P$2_S1") (pintype "bidirectional"))
      (node (ref "A04") (pin "N2") (pinfunction "D_N2") (pintype "open_collector"))
      (node (ref "A05") (pin "N2") (pinfunction "D_N2") (pintype "open_collector"))
      (node (ref "B03") (pin "S1") (pinfunction "P$2_S1") (pintype "bidirectional"))
    )
    (net (code "155") (name "AC09L") (class "Default")
      (node (ref "A03") (pin "D2") (pinfunction "P$2_D2") (pintype "bidirectional"))
      (node (ref "A05") (pin "P2") (pinfunction "E_P2") (pintype "open_collector"))
      (node (ref "B03") (pin "D2") (pinfunction "P$2_D2") (pintype "bidirectional"))
    )
    (net (code "156") (name "AC10L") (class "Default")
      (node (ref "A03") (pin "E2") (pinfunction "P$2_E2") (pintype "bidirectional"))
      (node (ref "A05") (pin "U2") (pinfunction "D_U2") (pintype "open_collector"))
      (node (ref "B03") (pin "E2") (pinfunction "P$2_E2") (pintype "bidirectional"))
    )
    (net (code "157") (name "AC11L") (class "Default")
      (node (ref "A03") (pin "H2") (pinfunction "P$2_H2") (pintype "bidirectional"))
      (node (ref "A05") (pin "V2") (pinfunction "E_V2") (pintype "open_collector"))
      (node (ref "B03") (pin "H2") (pinfunction "P$2_H2") (pintype "bidirectional"))
    )
    (net (code "158") (name "B06V1") (class "Default")
      (node (ref "B06") (pin "J1") (pinfunction "IN2_J1") (pintype "input"))
      (node (ref "B06") (pin "L2") (pinfunction "L2_L2") (pintype "input"))
      (node (ref "B06") (pin "N2") (pinfunction "N2_N2") (pintype "input"))
      (node (ref "B06") (pin "U2") (pinfunction "U2_U2") (pintype "input"))
      (node (ref "B06") (pin "V1") (pinfunction "P$1_V1") (pintype "passive"))
    )
    (net (code "159") (name "BAC00") (class "Default")
      (node (ref "A01") (pin "B1") (pinfunction "P$2_B1") (pintype "bidirectional"))
      (node (ref "A07") (pin "A1") (pinfunction "IN1_A1") (pintype "input"))
      (node (ref "B01") (pin "B1") (pinfunction "P$2_B1") (pintype "bidirectional"))
      (node (ref "B07") (pin "A1") (pinfunction "IN1_A1") (pintype "input"))
    )
    (net (code "160") (name "BAC01") (class "Default")
      (node (ref "A01") (pin "D1") (pinfunction "P$2_D1") (pintype "bidirectional"))
      (node (ref "A07") (pin "D1") (pinfunction "IN_D1") (pintype "input"))
      (node (ref "B01") (pin "D1") (pinfunction "P$2_D1") (pintype "bidirectional"))
      (node (ref "B07") (pin "D1") (pinfunction "IN_D1") (pintype "input"))
    )
    (net (code "161") (name "BAC02") (class "Default")
      (node (ref "A01") (pin "E1") (pinfunction "P$2_E1") (pintype "bidirectional"))
      (node (ref "A07") (pin "F1") (pinfunction "IN_F1") (pintype "input"))
      (node (ref "B01") (pin "E1") (pinfunction "P$2_E1") (pintype "bidirectional"))
      (node (ref "B07") (pin "F1") (pinfunction "IN_F1") (pintype "input"))
    )
    (net (code "162") (name "BAC03") (class "Default")
      (node (ref "A01") (pin "H1") (pinfunction "P$2_H1") (pintype "bidirectional"))
      (node (ref "B01") (pin "H1") (pinfunction "P$2_H1") (pintype "bidirectional"))
    )
    (net (code "163") (name "BAC04") (class "Default")
      (node (ref "A01") (pin "J1") (pinfunction "P$2_J1") (pintype "bidirectional"))
      (node (ref "A07") (pin "J1") (pinfunction "IN_J1") (pintype "input"))
      (node (ref "B01") (pin "J1") (pinfunction "P$2_J1") (pintype "bidirectional"))
      (node (ref "B07") (pin "J1") (pinfunction "IN_J1") (pintype "input"))
    )
    (net (code "164") (name "BAC05") (class "Default")
      (node (ref "A01") (pin "L1") (pinfunction "P$2_L1") (pintype "bidirectional"))
      (node (ref "A07") (pin "L1") (pinfunction "IN_L1") (pintype "input"))
      (node (ref "B01") (pin "L1") (pinfunction "P$2_L1") (pintype "bidirectional"))
      (node (ref "B07") (pin "L1") (pinfunction "IN_L1") (pintype "input"))
    )
    (net (code "165") (name "BAC06") (class "Default")
      (node (ref "A01") (pin "M1") (pinfunction "P$2_M1") (pintype "bidirectional"))
      (node (ref "A07") (pin "N1") (pinfunction "IN_N1") (pintype "input"))
      (node (ref "B01") (pin "M1") (pinfunction "P$2_M1") (pintype "bidirectional"))
      (node (ref "B07") (pin "N1") (pinfunction "IN_N1") (pintype "input"))
    )
    (net (code "166") (name "BAC07") (class "Default")
      (node (ref "A01") (pin "P1") (pinfunction "P$2_P1") (pintype "bidirectional"))
      (node (ref "A07") (pin "R1") (pinfunction "IN_R1") (pintype "input"))
      (node (ref "B01") (pin "P1") (pinfunction "P$2_P1") (pintype "bidirectional"))
      (node (ref "B07") (pin "R1") (pinfunction "IN_R1") (pintype "input"))
    )
    (net (code "167") (name "BAC08") (class "Default")
      (node (ref "A01") (pin "S1") (pinfunction "P$2_S1") (pintype "bidirectional"))
      (node (ref "A07") (pin "V1") (pinfunction "IN_V1") (pintype "input"))
      (node (ref "B01") (pin "S1") (pinfunction "P$2_S1") (pintype "bidirectional"))
      (node (ref "B07") (pin "V1") (pinfunction "IN_V1") (pintype "input"))
    )
    (net (code "168") (name "BAC09") (class "Default")
      (node (ref "A01") (pin "D2") (pinfunction "P$2_D2") (pintype "bidirectional"))
      (node (ref "A07") (pin "E2") (pinfunction "IN_E2") (pintype "input"))
      (node (ref "B01") (pin "D2") (pinfunction "P$2_D2") (pintype "bidirectional"))
      (node (ref "B07") (pin "E2") (pinfunction "IN_E2") (pintype "input"))
    )
    (net (code "169") (name "BAC10") (class "Default")
      (node (ref "A01") (pin "E2") (pinfunction "P$2_E2") (pintype "bidirectional"))
      (node (ref "A07") (pin "H2") (pinfunction "IN_H2") (pintype "input"))
      (node (ref "B01") (pin "E2") (pinfunction "P$2_E2") (pintype "bidirectional"))
      (node (ref "B07") (pin "H2") (pinfunction "IN_H2") (pintype "input"))
    )
    (net (code "170") (name "BAC11") (class "Default")
      (node (ref "A01") (pin "H2") (pinfunction "P$2_H2") (pintype "bidirectional"))
      (node (ref "A07") (pin "K2") (pinfunction "IN_K2") (pintype "input"))
      (node (ref "B01") (pin "H2") (pinfunction "P$2_H2") (pintype "bidirectional"))
      (node (ref "B07") (pin "K2") (pinfunction "IN_K2") (pintype "input"))
    )
    (net (code "171") (name "BIOP1") (class "Default")
      (node (ref "A01") (pin "K2") (pinfunction "P$2_K2") (pintype "bidirectional"))
      (node (ref "A06") (pin "P2") (pinfunction "P2_P2") (pintype "input"))
      (node (ref "B01") (pin "K2") (pinfunction "P$2_K2") (pintype "bidirectional"))
      (node (ref "B06") (pin "P2") (pinfunction "P2_P2") (pintype "input"))
    )
    (net (code "172") (name "BIOP2") (class "Default")
      (node (ref "A01") (pin "M2") (pinfunction "P$2_M2") (pintype "bidirectional"))
      (node (ref "A06") (pin "R2") (pinfunction "R2_R2") (pintype "input"))
      (node (ref "B01") (pin "M2") (pinfunction "P$2_M2") (pintype "bidirectional"))
      (node (ref "B06") (pin "R2") (pinfunction "R2_R2") (pintype "input"))
    )
    (net (code "173") (name "BIOP4") (class "Default")
      (node (ref "A01") (pin "P2") (pinfunction "P$2_P2") (pintype "bidirectional"))
      (node (ref "A06") (pin "S2") (pinfunction "S2_S2") (pintype "input"))
      (node (ref "B01") (pin "P2") (pinfunction "P$2_P2") (pintype "bidirectional"))
      (node (ref "B06") (pin "S2") (pinfunction "S2_S2") (pintype "input"))
    )
    (net (code "174") (name "BMB00H") (class "Default")
      (node (ref "A02") (pin "B1") (pinfunction "P$2_B1") (pintype "bidirectional"))
      (node (ref "B02") (pin "B1") (pinfunction "P$2_B1") (pintype "bidirectional"))
    )
    (net (code "175") (name "BMB01H") (class "Default")
      (node (ref "A02") (pin "D1") (pinfunction "P$2_D1") (pintype "bidirectional"))
      (node (ref "B02") (pin "D1") (pinfunction "P$2_D1") (pintype "bidirectional"))
    )
    (net (code "176") (name "BMB02H") (class "Default")
      (node (ref "A02") (pin "E1") (pinfunction "P$2_E1") (pintype "bidirectional"))
      (node (ref "B02") (pin "E1") (pinfunction "P$2_E1") (pintype "bidirectional"))
    )
    (net (code "177") (name "BMB03H") (class "Default")
      (node (ref "A02") (pin "J1") (pinfunction "P$2_J1") (pintype "bidirectional"))
      (node (ref "A06") (pin "D2") (pinfunction "D2_D2") (pintype "input"))
      (node (ref "B02") (pin "J1") (pinfunction "P$2_J1") (pintype "bidirectional"))
      (node (ref "B06") (pin "D2") (pinfunction "D2_D2") (pintype "input"))
    )
    (net (code "178") (name "BMB03L") (class "Default")
      (node (ref "A02") (pin "H1") (pinfunction "P$2_H1") (pintype "bidirectional"))
      (node (ref "B02") (pin "H1") (pinfunction "P$2_H1") (pintype "bidirectional"))
    )
    (net (code "179") (name "BMB04H") (class "Default")
      (node (ref "A02") (pin "M1") (pinfunction "P$2_M1") (pintype "bidirectional"))
      (node (ref "A06") (pin "E2") (pinfunction "E2_E2") (pintype "input"))
      (node (ref "B02") (pin "M1") (pinfunction "P$2_M1") (pintype "bidirectional"))
      (node (ref "B06") (pin "E2") (pinfunction "E2_E2") (pintype "input"))
    )
    (net (code "180") (name "BMB04L") (class "Default")
      (node (ref "A02") (pin "L1") (pinfunction "P$2_L1") (pintype "bidirectional"))
      (node (ref "B02") (pin "L1") (pinfunction "P$2_L1") (pintype "bidirectional"))
    )
    (net (code "181") (name "BMB05H") (class "Default")
      (node (ref "A02") (pin "S1") (pinfunction "P$2_S1") (pintype "bidirectional"))
      (node (ref "A06") (pin "F2") (pinfunction "F2_F2") (pintype "input"))
      (node (ref "B02") (pin "S1") (pinfunction "P$2_S1") (pintype "bidirectional"))
      (node (ref "B06") (pin "F2") (pinfunction "F2_F2") (pintype "input"))
    )
    (net (code "182") (name "BMB05L") (class "Default")
      (node (ref "A02") (pin "P1") (pinfunction "P$2_P1") (pintype "bidirectional"))
      (node (ref "B02") (pin "P1") (pinfunction "P$2_P1") (pintype "bidirectional"))
    )
    (net (code "183") (name "BMB06H") (class "Default")
      (node (ref "A02") (pin "E2") (pinfunction "P$2_E2") (pintype "bidirectional"))
      (node (ref "B02") (pin "E2") (pinfunction "P$2_E2") (pintype "bidirectional"))
    )
    (net (code "184") (name "BMB06L") (class "Default")
      (node (ref "A02") (pin "D2") (pinfunction "P$2_D2") (pintype "bidirectional"))
      (node (ref "A06") (pin "H2") (pinfunction "H2_H2") (pintype "input"))
      (node (ref "B02") (pin "D2") (pinfunction "P$2_D2") (pintype "bidirectional"))
      (node (ref "B06") (pin "H2") (pinfunction "H2_H2") (pintype "input"))
    )
    (net (code "185") (name "BMB07H") (class "Default")
      (node (ref "A02") (pin "K2") (pinfunction "P$2_K2") (pintype "bidirectional"))
      (node (ref "B02") (pin "K2") (pinfunction "P$2_K2") (pintype "bidirectional"))
    )
    (net (code "186") (name "BMB07L") (class "Default")
      (node (ref "A02") (pin "H2") (pinfunction "P$2_H2") (pintype "bidirectional"))
      (node (ref "A06") (pin "J2") (pinfunction "J2_J2") (pintype "input"))
      (node (ref "B02") (pin "H2") (pinfunction "P$2_H2") (pintype "bidirectional"))
      (node (ref "B06") (pin "J2") (pinfunction "J2_J2") (pintype "input"))
    )
    (net (code "187") (name "BMB08H") (class "Default")
      (node (ref "A02") (pin "P2") (pinfunction "P$2_P2") (pintype "bidirectional"))
      (node (ref "B02") (pin "P2") (pinfunction "P$2_P2") (pintype "bidirectional"))
      (node (ref "B06") (pin "K2") (pinfunction "K2_K2") (pintype "input"))
    )
    (net (code "188") (name "BMB08L") (class "Default")
      (node (ref "A02") (pin "M2") (pinfunction "P$2_M2") (pintype "bidirectional"))
      (node (ref "A06") (pin "K2") (pinfunction "K2_K2") (pintype "input"))
      (node (ref "B02") (pin "M2") (pinfunction "P$2_M2") (pintype "bidirectional"))
    )
    (net (code "189") (name "BMB09H") (class "Default")
      (node (ref "A02") (pin "S2") (pinfunction "P$2_S2") (pintype "bidirectional"))
      (node (ref "A07") (pin "M2") (pinfunction "IN_M2") (pintype "input"))
      (node (ref "B02") (pin "S2") (pinfunction "P$2_S2") (pintype "bidirectional"))
      (node (ref "B07") (pin "M2") (pinfunction "IN_M2") (pintype "input"))
    )
    (net (code "190") (name "BMB10H") (class "Default")
      (node (ref "A02") (pin "T2") (pinfunction "P$2_T2") (pintype "bidirectional"))
      (node (ref "A07") (pin "P2") (pinfunction "IN_P2") (pintype "input"))
      (node (ref "B02") (pin "T2") (pinfunction "P$2_T2") (pintype "bidirectional"))
      (node (ref "B07") (pin "P2") (pinfunction "IN_P2") (pintype "input"))
    )
    (net (code "191") (name "BMB11H") (class "Default")
      (node (ref "A02") (pin "V2") (pinfunction "P$2_V2") (pintype "bidirectional"))
      (node (ref "A07") (pin "S2") (pinfunction "IN_S2") (pintype "input"))
      (node (ref "B02") (pin "V2") (pinfunction "P$2_V2") (pintype "bidirectional"))
      (node (ref "B07") (pin "S2") (pinfunction "IN_S2") (pintype "input"))
    )
    (net (code "192") (name "CLEAR_AC_L") (class "Default")
      (node (ref "A03") (pin "P2") (pinfunction "P$2_P2") (pintype "bidirectional"))
      (node (ref "A05") (pin "D1") (pinfunction "D_D1") (pintype "open_collector"))
      (node (ref "B03") (pin "P2") (pinfunction "P$2_P2") (pintype "bidirectional"))
    )
    (net (code "193") (name "GND") (class "Default")
      (node (ref "A04") (pin "L2") (pinfunction "B_L2") (pintype "input"))
      (node (ref "A04") (pin "T2") (pinfunction "C_T2") (pintype "input"))
      (node (ref "A05") (pin "B1") (pinfunction "B_B1") (pintype "input"))
      (node (ref "A05") (pin "C1") (pinfunction "C_C1") (pintype "input"))
      (node (ref "A05") (pin "H1") (pinfunction "B_H1") (pintype "input"))
      (node (ref "A14") (pin "C1") (pinfunction "D_C1") (pintype "input"))
      (node (ref "A14") (pin "E2") (pinfunction "D_E2") (pintype "input"))
      (node (ref "A14") (pin "J1") (pinfunction "D_J1") (pintype "input"))
      (node (ref "A14") (pin "M2") (pinfunction "D_M2") (pintype "input"))
      (node (ref "A14") (pin "P1") (pinfunction "D_P1") (pintype "input"))
      (node (ref "A14") (pin "T2") (pinfunction "D_T2") (pintype "input"))
      (node (ref "A23") (pin "A1") (pinfunction "P$2_A1") (pintype "bidirectional"))
      (node (ref "A23") (pin "C1") (pinfunction "P$2_C1") (pintype "bidirectional"))
      (node (ref "A23") (pin "C2") (pinfunction "P$2_C2") (pintype "bidirectional"))
      (node (ref "A23") (pin "F1") (pinfunction "P$2_F1") (pintype "bidirectional"))
      (node (ref "A23") (pin "F2") (pinfunction "P$2_F2") (pintype "bidirectional"))
      (node (ref "A23") (pin "J2") (pinfunction "P$2_J2") (pintype "bidirectional"))
      (node (ref "A23") (pin "K1") (pinfunction "P$2_K1") (pintype "bidirectional"))
      (node (ref "A23") (pin "L2") (pinfunction "P$2_L2") (pintype "bidirectional"))
      (node (ref "A23") (pin "N1") (pinfunction "P$2_N1") (pintype "bidirectional"))
      (node (ref "A23") (pin "N2") (pinfunction "P$2_N2") (pintype "bidirectional"))
      (node (ref "A23") (pin "R1") (pinfunction "P$2_R1") (pintype "bidirectional"))
      (node (ref "A23") (pin "R2") (pinfunction "P$2_R2") (pintype "bidirectional"))
      (node (ref "A23") (pin "T1") (pinfunction "P$2_T1") (pintype "bidirectional"))
      (node (ref "A23") (pin "U2") (pinfunction "P$2_U2") (pintype "bidirectional"))
      (node (ref "A24") (pin "A1") (pinfunction "P$2_A1") (pintype "bidirectional"))
      (node (ref "A24") (pin "C1") (pinfunction "P$2_C1") (pintype "bidirectional"))
      (node (ref "A24") (pin "C2") (pinfunction "P$2_C2") (pintype "bidirectional"))
      (node (ref "A24") (pin "F1") (pinfunction "P$2_F1") (pintype "bidirectional"))
      (node (ref "A24") (pin "F2") (pinfunction "P$2_F2") (pintype "bidirectional"))
      (node (ref "A24") (pin "J2") (pinfunction "P$2_J2") (pintype "bidirectional"))
      (node (ref "A24") (pin "K1") (pinfunction "P$2_K1") (pintype "bidirectional"))
      (node (ref "A24") (pin "L2") (pinfunction "P$2_L2") (pintype "bidirectional"))
      (node (ref "A24") (pin "N1") (pinfunction "P$2_N1") (pintype "bidirectional"))
      (node (ref "A24") (pin "N2") (pinfunction "P$2_N2") (pintype "bidirectional"))
      (node (ref "A24") (pin "R1") (pinfunction "P$2_R1") (pintype "bidirectional"))
      (node (ref "A24") (pin "R2") (pinfunction "P$2_R2") (pintype "bidirectional"))
      (node (ref "A24") (pin "T1") (pinfunction "P$2_T1") (pintype "bidirectional"))
      (node (ref "A24") (pin "U2") (pinfunction "P$2_U2") (pintype "bidirectional"))
      (node (ref "B23") (pin "A1") (pinfunction "P$2_A1") (pintype "bidirectional"))
      (node (ref "B23") (pin "C1") (pinfunction "P$2_C1") (pintype "bidirectional"))
      (node (ref "B23") (pin "C2") (pinfunction "P$2_C2") (pintype "bidirectional"))
      (node (ref "B23") (pin "F1") (pinfunction "P$2_F1") (pintype "bidirectional"))
      (node (ref "B23") (pin "F2") (pinfunction "P$2_F2") (pintype "bidirectional"))
      (node (ref "B23") (pin "J2") (pinfunction "P$2_J2") (pintype "bidirectional"))
      (node (ref "B23") (pin "K1") (pinfunction "P$2_K1") (pintype "bidirectional"))
      (node (ref "B23") (pin "L2") (pinfunction "P$2_L2") (pintype "bidirectional"))
      (node (ref "B23") (pin "N1") (pinfunction "P$2_N1") (pintype "bidirectional"))
      (node (ref "B23") (pin "N2") (pinfunction "P$2_N2") (pintype "bidirectional"))
      (node (ref "B23") (pin "R1") (pinfunction "P$2_R1") (pintype "bidirectional"))
      (node (ref "B23") (pin "R2") (pinfunction "P$2_R2") (pintype "bidirectional"))
      (node (ref "B23") (pin "T1") (pinfunction "P$2_T1") (pintype "bidirectional"))
      (node (ref "B23") (pin "U2") (pinfunction "P$2_U2") (pintype "bidirectional"))
      (node (ref "B24") (pin "A1") (pinfunction "P$2_A1") (pintype "bidirectional"))
      (node (ref "B24") (pin "C1") (pinfunction "P$2_C1") (pintype "bidirectional"))
      (node (ref "B24") (pin "C2") (pinfunction "P$2_C2") (pintype "bidirectional"))
      (node (ref "B24") (pin "F1") (pinfunction "P$2_F1") (pintype "bidirectional"))
      (node (ref "B24") (pin "F2") (pinfunction "P$2_F2") (pintype "bidirectional"))
      (node (ref "B24") (pin "J2") (pinfunction "P$2_J2") (pintype "bidirectional"))
      (node (ref "B24") (pin "K1") (pinfunction "P$2_K1") (pintype "bidirectional"))
      (node (ref "B24") (pin "L2") (pinfunction "P$2_L2") (pintype "bidirectional"))
      (node (ref "B24") (pin "N1") (pinfunction "P$2_N1") (pintype "bidirectional"))
      (node (ref "B24") (pin "N2") (pinfunction "P$2_N2") (pintype "bidirectional"))
      (node (ref "B24") (pin "R1") (pinfunction "P$2_R1") (pintype "bidirectional"))
      (node (ref "B24") (pin "R2") (pinfunction "P$2_R2") (pintype "bidirectional"))
      (node (ref "B24") (pin "T1") (pinfunction "P$2_T1") (pintype "bidirectional"))
      (node (ref "B24") (pin "U2") (pinfunction "P$2_U2") (pintype "bidirectional"))
      (node (ref "C3") (pin "2") (pinfunction "2_2") (pintype "passive"))
      (node (ref "R4") (pin "1") (pinfunction "1_1") (pintype "passive"))
      (node (ref "S3") (pin "2") (pinfunction "P_2") (pintype "passive"))
      (node (ref "S4") (pin "2") (pinfunction "P_2") (pintype "passive"))
    )
    (net (code "194") (name "INITIALIZE") (class "Default")
      (node (ref "A01") (pin "V2") (pinfunction "P$2_V2") (pintype "bidirectional"))
      (node (ref "A06") (pin "H1") (pinfunction "IN1_H1") (pintype "input"))
      (node (ref "B01") (pin "V2") (pinfunction "P$2_V2") (pintype "bidirectional"))
      (node (ref "B06") (pin "H1") (pinfunction "IN1_H1") (pintype "input"))
    )
    (net (code "195") (name "INT_REQ_L") (class "Default")
      (node (ref "A03") (pin "M2") (pinfunction "P$2_M2") (pintype "bidirectional"))
      (node (ref "A04") (pin "V2") (pinfunction "E_V2") (pintype "open_collector"))
      (node (ref "B03") (pin "M2") (pinfunction "P$2_M2") (pintype "bidirectional"))
    )
    (net (code "196") (name "I_LINE") (class "Default")
      (node (ref "A03") (pin "V2") (pinfunction "P$2_V2") (pintype "bidirectional"))
      (node (ref "B03") (pin "V2") (pinfunction "P$2_V2") (pintype "bidirectional"))
    )
    (net (code "197") (name "I_RUN") (class "Default")
      (node (ref "A03") (pin "S2") (pinfunction "P$2_S2") (pintype "bidirectional"))
      (node (ref "B03") (pin "S2") (pinfunction "P$2_S2") (pintype "bidirectional"))
    )
    (net (code "198") (name "I_TS1") (class "Default")
      (node (ref "A01") (pin "T2") (pinfunction "P$2_T2") (pintype "bidirectional"))
      (node (ref "B01") (pin "T2") (pinfunction "P$2_T2") (pintype "bidirectional"))
    )
    (net (code "199") (name "I_TS3") (class "Default")
      (node (ref "A01") (pin "S2") (pinfunction "P$2_S2") (pintype "bidirectional"))
      (node (ref "B01") (pin "S2") (pinfunction "P$2_S2") (pintype "bidirectional"))
    )
    (net (code "200") (name "I_TT_INST") (class "Default")
      (node (ref "A03") (pin "T2") (pinfunction "P$2_T2") (pintype "bidirectional"))
      (node (ref "B03") (pin "T2") (pinfunction "P$2_T2") (pintype "bidirectional"))
    )
    (net (code "201") (name "Net-(A04J-A)") (class "Default")
      (node (ref "A04") (pin "R2") (pinfunction "A_R2") (pintype "input"))
      (node (ref "A08") (pin "N2") (pinfunction "OUT_N2") (pintype "output"))
    )
    (net (code "202") (name "Net-(A04J-B)") (class "Default")
      (node (ref "A04") (pin "S2") (pinfunction "B_S2") (pintype "input"))
      (node (ref "A08") (pin "L2") (pinfunction "OUT_L2") (pintype "output"))
    )
    (net (code "203") (name "Net-(A07A-IN2)") (class "Default")
      (node (ref "A06") (pin "V2") (pinfunction "V2_V2") (pintype "output"))
      (node (ref "A07") (pin "C1") (pinfunction "IN2_C1") (pintype "input"))
    )
    (net (code "204") (name "Net-(A08D-IN)") (class "Default")
      (node (ref "A08") (pin "E2") (pinfunction "IN_E2") (pintype "input"))
      (node (ref "A08") (pin "V1") (pinfunction "IN_V1") (pintype "input"))
      (node (ref "A11") (pin "C1") (pinfunction "OUT_C1") (pintype "output"))
    )
    (net (code "205") (name "Net-(A08H-OUT)") (class "Default")
      (node (ref "A08") (pin "J2") (pinfunction "OUT_J2") (pintype "output"))
      (node (ref "A10") (pin "H1") (pinfunction "C_H1") (pintype "input"))
      (node (ref "A11") (pin "H1") (pinfunction "IN1_H1") (pintype "input"))
    )
    (net (code "206") (name "Net-(A08J-IN)") (class "Default")
      (node (ref "A08") (pin "K2") (pinfunction "IN_K2") (pintype "input"))
      (node (ref "A09") (pin "V1") (pinfunction "OUT_V1") (pintype "output"))
    )
    (net (code "207") (name "Net-(A08L-IN)") (class "Default")
      (node (ref "A08") (pin "M2") (pinfunction "IN_M2") (pintype "input"))
      (node (ref "A09") (pin "D1") (pinfunction "OUT_D1") (pintype "output"))
    )
    (net (code "208") (name "Net-(A08N-IN)") (class "Default")
      (node (ref "A08") (pin "P2") (pinfunction "IN_P2") (pintype "input"))
      (node (ref "A11") (pin "N1") (pinfunction "OUT_N1") (pintype "output"))
    )
    (net (code "209") (name "Net-(A08N-OUT)") (class "Default")
      (node (ref "A08") (pin "R2") (pinfunction "OUT_R2") (pintype "output"))
      (node (ref "A10") (pin "N2") (pinfunction "S_N2") (pintype "input"))
    )
    (net (code "210") (name "Net-(A08P-IN)") (class "Default")
      (node (ref "A08") (pin "S2") (pinfunction "IN_S2") (pintype "input"))
      (node (ref "A11") (pin "S1") (pinfunction "OUT_S1") (pintype "output"))
    )
    (net (code "211") (name "Net-(A08R-OUT)") (class "Default")
      (node (ref "A08") (pin "V2") (pinfunction "OUT_V2") (pintype "output"))
      (node (ref "A12") (pin "D1") (pinfunction "IN4_D1") (pintype "input"))
      (node (ref "A12") (pin "H2") (pinfunction "IN4_H2") (pintype "input"))
      (node (ref "A12") (pin "K1") (pinfunction "IN4_K1") (pintype "input"))
      (node (ref "A12") (pin "R1") (pinfunction "IN4_R1") (pintype "input"))
      (node (ref "A18") (pin "D1") (pinfunction "IN4_D1") (pintype "input"))
      (node (ref "A18") (pin "K1") (pinfunction "IN4_K1") (pintype "input"))
      (node (ref "A18") (pin "N2") (pinfunction "IN4_N2") (pintype "input"))
      (node (ref "A18") (pin "R1") (pinfunction "IN4_R1") (pintype "input"))
    )
    (net (code "212") (name "Net-(A09A-IN1)") (class "Default")
      (node (ref "A09") (pin "A1") (pinfunction "IN1_A1") (pintype "input"))
      (node (ref "A17") (pin "C1") (pinfunction "OUT_C1") (pintype "output"))
    )
    (net (code "213") (name "Net-(A09A-IN2)") (class "Default")
      (node (ref "A09") (pin "B1") (pinfunction "IN2_B1") (pintype "input"))
      (node (ref "A11") (pin "K1") (pinfunction "OUT_K1") (pintype "output"))
    )
    (net (code "214") (name "Net-(A09A-IN3)") (class "Default")
      (node (ref "A09") (pin "C1") (pinfunction "IN3_C1") (pintype "input"))
      (node (ref "A17") (pin "S1") (pinfunction "OUT_S1") (pintype "output"))
    )
    (net (code "215") (name "Net-(A09D-OUT)") (class "Default")
      (node (ref "A09") (pin "H2") (pinfunction "OUT_H2") (pintype "output"))
      (node (ref "A09") (pin "P1") (pinfunction "IN1_P1") (pintype "input"))
      (node (ref "A11") (pin "L2") (pinfunction "IN1_L2") (pintype "input"))
    )
    (net (code "216") (name "Net-(A09J-IN1)") (class "Default")
      (node (ref "A09") (pin "T2") (pinfunction "IN1_T2") (pintype "input"))
      (node (ref "A10") (pin "C1") (pinfunction "D_C1") (pintype "input"))
      (node (ref "A10") (pin "H2") (pinfunction "1_H2") (pintype "output"))
    )
    (net (code "217") (name "Net-(A09J-IN2)") (class "Default")
      (node (ref "A09") (pin "U2") (pinfunction "IN2_U2") (pintype "input"))
      (node (ref "A10") (pin "J1") (pinfunction "D_J1") (pintype "input"))
      (node (ref "A10") (pin "P2") (pinfunction "1_P2") (pintype "output"))
    )
    (net (code "218") (name "Net-(A09J-IN3)") (class "Default")
      (node (ref "A09") (pin "V2") (pinfunction "IN3_V2") (pintype "input"))
      (node (ref "A10") (pin "P1") (pinfunction "D_P1") (pintype "input"))
      (node (ref "A10") (pin "V2") (pinfunction "1_V2") (pintype "output"))
    )
    (net (code "219") (name "Net-(A10A-0)") (class "Default")
      (node (ref "A10") (pin "F1") (pinfunction "0_F1") (pintype "output"))
      (node (ref "A17") (pin "B1") (pinfunction "IN2_B1") (pintype "input"))
      (node (ref "A17") (pin "D1") (pinfunction "IN1_D1") (pintype "input"))
    )
    (net (code "220") (name "Net-(A10A-C)") (class "Default")
      (node (ref "A10") (pin "B1") (pinfunction "C_B1") (pintype "input"))
      (node (ref "A16") (pin "P1") (pinfunction "OUT_P1") (pintype "output"))
      (node (ref "A17") (pin "A1") (pinfunction "IN1_A1") (pintype "input"))
    )
    (net (code "221") (name "Net-(A10A-S)") (class "Default")
      (node (ref "A10") (pin "D1") (pinfunction "S_D1") (pintype "input"))
      (node (ref "A10") (pin "J2") (pinfunction "0_J2") (pintype "output"))
    )
    (net (code "222") (name "Net-(A10D-S)") (class "Default")
      (node (ref "A10") (pin "F2") (pinfunction "S_F2") (pintype "input"))
      (node (ref "A16") (pin "H1") (pinfunction "OUT_H1") (pintype "output"))
    )
    (net (code "223") (name "Net-(A10E-0)") (class "Default")
      (node (ref "A10") (pin "M1") (pinfunction "0_M1") (pintype "output"))
      (node (ref "A11") (pin "H2") (pinfunction "IN1_H2") (pintype "input"))
      (node (ref "A11") (pin "J1") (pinfunction "IN2_J1") (pintype "input"))
    )
    (net (code "224") (name "Net-(A10E-S)") (class "Default")
      (node (ref "A10") (pin "K1") (pinfunction "S_K1") (pintype "input"))
      (node (ref "A10") (pin "R2") (pinfunction "0_R2") (pintype "output"))
    )
    (net (code "225") (name "Net-(A10F-C)") (class "Default")
      (node (ref "A10") (pin "L2") (pinfunction "C_L2") (pintype "input"))
      (node (ref "A12") (pin "V2") (pinfunction "OUT_V2") (pintype "output"))
    )
    (net (code "226") (name "Net-(A10G-0)") (class "Default")
      (node (ref "A10") (pin "U1") (pinfunction "0_U1") (pintype "output"))
      (node (ref "A17") (pin "R1") (pinfunction "IN2_R1") (pintype "input"))
      (node (ref "A17") (pin "T2") (pinfunction "IN1_T2") (pintype "input"))
    )
    (net (code "227") (name "Net-(A10G-C)") (class "Default")
      (node (ref "A10") (pin "N1") (pinfunction "C_N1") (pintype "input"))
      (node (ref "A16") (pin "E1") (pinfunction "OUT_E1") (pintype "output"))
      (node (ref "A17") (pin "P1") (pinfunction "IN1_P1") (pintype "input"))
    )
    (net (code "228") (name "Net-(A10G-S)") (class "Default")
      (node (ref "A10") (pin "R1") (pinfunction "S_R1") (pintype "input"))
      (node (ref "A10") (pin "V1") (pinfunction "0_V1") (pintype "output"))
    )
    (net (code "229") (name "Net-(A10H-C)") (class "Default")
      (node (ref "A10") (pin "S2") (pinfunction "C_S2") (pintype "input"))
      (node (ref "A16") (pin "J2") (pinfunction "OUT_J2") (pintype "output"))
    )
    (net (code "230") (name "Net-(A10H-S)") (class "Default")
      (node (ref "A10") (pin "U2") (pinfunction "S_U2") (pintype "input"))
      (node (ref "A16") (pin "K1") (pinfunction "OUT_K1") (pintype "output"))
    )
    (net (code "231") (name "Net-(A11B-IN1)") (class "Default")
      (node (ref "A11") (pin "D1") (pinfunction "IN1_D1") (pintype "input"))
      (node (ref "A11") (pin "V2") (pinfunction "OUT_V2") (pintype "output"))
    )
    (net (code "232") (name "Net-(A11C-IN1)") (class "Default")
      (node (ref "A11") (pin "D2") (pinfunction "IN1_D2") (pintype "input"))
      (node (ref "A12") (pin "L1") (pinfunction "OUT_L1") (pintype "output"))
    )
    (net (code "233") (name "Net-(A11G-OUT)") (class "Default")
      (node (ref "A11") (pin "K2") (pinfunction "OUT_K2") (pintype "output"))
      (node (ref "A11") (pin "L1") (pinfunction "IN1_L1") (pintype "input"))
    )
    (net (code "234") (name "Net-(A11K-IN1)") (class "Default")
      (node (ref "A11") (pin "P2") (pinfunction "IN1_P2") (pintype "input"))
      (node (ref "A13") (pin "K1") (pinfunction "H2_K1") (pintype "output"))
      (node (ref "A17") (pin "M2") (pinfunction "IN2_M2") (pintype "input"))
    )
    (net (code "235") (name "Net-(A11K-IN2)") (class "Default")
      (node (ref "A11") (pin "R2") (pinfunction "IN2_R2") (pintype "input"))
      (node (ref "A15") (pin "J1") (pinfunction "OUT_J1") (pintype "output"))
      (node (ref "A15") (pin "K1") (pinfunction "IN1_K1") (pintype "input"))
    )
    (net (code "236") (name "Net-(A13-PadM2)") (class "Default")
      (node (ref "A13") (pin "M2") (pinfunction "M2_M2") (pintype "passive"))
      (node (ref "A13") (pin "R2") (pinfunction "R2_R2") (pintype "passive"))
      (node (ref "A13") (pin "S2") (pinfunction "S2_S2") (pintype "passive"))
      (node (ref "A13") (pin "U2") (pinfunction "U2_U2") (pintype "passive"))
      (node (ref "A13") (pin "V2") (pinfunction "V2_V2") (pintype "passive"))
    )
    (net (code "237") (name "Net-(A13-PadP1)") (class "Default")
      (node (ref "A13") (pin "P1") (pinfunction "P1_P1") (pintype "passive"))
      (node (ref "A13") (pin "V1") (pinfunction "V1_V1") (pintype "passive"))
    )
    (net (code "238") (name "Net-(A13E-M2)") (class "Default")
      (node (ref "A13") (pin "B1") (pinfunction "V2_B1") (pintype "passive"))
      (node (ref "A13") (pin "D1") (pinfunction "U2_D1") (pintype "passive"))
      (node (ref "A13") (pin "D2") (pinfunction "M2_D2") (pintype "passive"))
      (node (ref "A13") (pin "E1") (pinfunction "S2_E1") (pintype "passive"))
      (node (ref "A13") (pin "F1") (pinfunction "R2_F1") (pintype "passive"))
      (node (ref "A13") (pin "H1") (pinfunction "P2_H1") (pintype "passive"))
    )
    (net (code "239") (name "Net-(A13E-P1)") (class "Default")
      (node (ref "A13") (pin "A1") (pinfunction "V1_A1") (pintype "passive"))
      (node (ref "A13") (pin "C1") (pinfunction "P1_C1") (pintype "passive"))
    )
    (net (code "240") (name "Net-(A14A-S)") (class "Default")
      (node (ref "A14") (pin "D1") (pinfunction "S_D1") (pintype "input"))
      (node (ref "A17") (pin "F2") (pinfunction "OUT_F2") (pintype "output"))
    )
    (net (code "241") (name "Net-(A14D-S)") (class "Default")
      (node (ref "A14") (pin "F2") (pinfunction "S_F2") (pintype "input"))
      (node (ref "A16") (pin "N2") (pinfunction "OUT_N2") (pintype "output"))
    )
    (net (code "242") (name "Net-(A15E-IN3)") (class "Default")
      (node (ref "A15") (pin "H1") (pinfunction "IN3_H1") (pintype "input"))
      (node (ref "A15") (pin "N1") (pinfunction "OUT_N1") (pintype "output"))
      (node (ref "A17") (pin "L2") (pinfunction "IN1_L2") (pintype "input"))
    )
    (net (code "243") (name "Net-(A15H-IN1)") (class "Default")
      (node (ref "A13") (pin "N1") (pinfunction "N1_N1") (pintype "input"))
      (node (ref "A15") (pin "N2") (pinfunction "IN1_N2") (pintype "input"))
      (node (ref "A15") (pin "P2") (pinfunction "IN2_P2") (pintype "input"))
      (node (ref "A16") (pin "S1") (pinfunction "OUT_S1") (pintype "output"))
    )
    (net (code "244") (name "Net-(A16G-IN)") (class "Default")
      (node (ref "A16") (pin "F1") (pinfunction "IN_F1") (pintype "input"))
      (node (ref "A17") (pin "S2") (pinfunction "OUT_S2") (pintype "output"))
    )
    (net (code "245") (name "Net-(A16H-IN)") (class "Default")
      (node (ref "A16") (pin "H2") (pinfunction "IN_H2") (pintype "input"))
      (node (ref "A17") (pin "K1") (pinfunction "OUT_K1") (pintype "output"))
    )
    (net (code "246") (name "Net-(A16I-IN)") (class "Default")
      (node (ref "A16") (pin "J1") (pinfunction "IN_J1") (pintype "input"))
      (node (ref "A17") (pin "N1") (pinfunction "OUT_N1") (pintype "output"))
    )
    (net (code "247") (name "Net-(A16J-IN)") (class "Default")
      (node (ref "A16") (pin "K2") (pinfunction "IN_K2") (pintype "input"))
      (node (ref "A19") (pin "F2") (pinfunction "F2_F2") (pintype "output"))
    )
    (net (code "248") (name "Net-(A16K-IN)") (class "Default")
      (node (ref "A16") (pin "L1") (pinfunction "IN_L1") (pintype "input"))
      (node (ref "A18") (pin "E1") (pinfunction "OUT_E1") (pintype "output"))
    )
    (net (code "249") (name "Net-(A16K-OUT)") (class "Default")
      (node (ref "A16") (pin "M1") (pinfunction "OUT_M1") (pintype "output"))
      (node (ref "A17") (pin "D2") (pinfunction "IN1_D2") (pintype "input"))
    )
    (net (code "250") (name "Net-(A16L-IN)") (class "Default")
      (node (ref "A16") (pin "M2") (pinfunction "IN_M2") (pintype "input"))
      (node (ref "A18") (pin "J2") (pinfunction "OUT_J2") (pintype "output"))
    )
    (net (code "251") (name "Net-(A16O-IN)") (class "Default")
      (node (ref "A16") (pin "R1") (pinfunction "IN_R1") (pintype "input"))
      (node (ref "A19") (pin "T2") (pinfunction "F2_T2") (pintype "output"))
    )
    (net (code "252") (name "Net-(A17B-OUT)") (class "Default")
      (node (ref "A17") (pin "F1") (pinfunction "OUT_F1") (pintype "output"))
      (node (ref "A17") (pin "P2") (pinfunction "IN1_P2") (pintype "input"))
    )
    (net (code "253") (name "Net-(A17G-OUT)") (class "Default")
      (node (ref "A17") (pin "K2") (pinfunction "OUT_K2") (pintype "output"))
      (node (ref "A19") (pin "H2") (pinfunction "H2_H2") (pintype "input"))
      (node (ref "A19") (pin "J2") (pinfunction "J2_J2") (pintype "input"))
      (node (ref "A19") (pin "K2") (pinfunction "K2_K2") (pintype "input"))
    )
    (net (code "254") (name "Net-(A17H-IN1)") (class "Default")
      (node (ref "A17") (pin "L1") (pinfunction "IN1_L1") (pintype "input"))
      (node (ref "A17") (pin "V2") (pinfunction "OUT_V2") (pintype "output"))
    )
    (net (code "255") (name "Net-(A19-PadD2)") (class "Default")
      (node (ref "A19") (pin "D2") (pinfunction "D2_D2") (pintype "passive"))
      (node (ref "A19") (pin "E2") (pinfunction "E2_E2") (pintype "passive"))
    )
    (net (code "256") (name "Net-(A19-PadE1)") (class "Default")
      (node (ref "A19") (pin "E1") (pinfunction "E1_E1") (pintype "passive"))
      (node (ref "C1") (pin "+") (pinfunction "+_+") (pintype "passive"))
    )
    (net (code "257") (name "Net-(A19-PadF1)") (class "Default")
      (node (ref "A19") (pin "F1") (pinfunction "F1_F1") (pintype "passive"))
      (node (ref "C1") (pin "-") (pinfunction "-_-") (pintype "passive"))
    )
    (net (code "258") (name "Net-(A19D-D2)") (class "Default")
      (node (ref "A19") (pin "R2") (pinfunction "E2_R2") (pintype "passive"))
      (node (ref "A19") (pin "V2") (pinfunction "D2_V2") (pintype "passive"))
    )
    (net (code "259") (name "Net-(A19D-E1)") (class "Default")
      (node (ref "A19") (pin "P1") (pinfunction "E1_P1") (pintype "passive"))
      (node (ref "A19") (pin "S2") (pinfunction "L2_S2") (pintype "passive"))
      (node (ref "C2") (pin "+") (pinfunction "+_+") (pintype "passive"))
    )
    (net (code "260") (name "Net-(A19D-F1)") (class "Default")
      (node (ref "A19") (pin "R1") (pinfunction "F1_R1") (pintype "passive"))
      (node (ref "C2") (pin "-") (pinfunction "-_-") (pintype "passive"))
    )
    (net (code "261") (name "Net-(A20C-1A)") (class "Default")
      (node (ref "A20") (pin "E1") (pinfunction "1A_E1") (pintype "input"))
      (node (ref "R2") (pin "1") (pinfunction "1_1") (pintype "passive"))
      (node (ref "S4") (pin "3") (pinfunction "S_3") (pintype "passive"))
    )
    (net (code "262") (name "Net-(A20C-1B)") (class "Default")
      (node (ref "A20") (pin "A1") (pinfunction "1B_A1") (pintype "input"))
      (node (ref "R1") (pin "1") (pinfunction "1_1") (pintype "passive"))
      (node (ref "S4") (pin "1") (pinfunction "O_1") (pintype "passive"))
    )
    (net (code "263") (name "Net-(A20C-4A)") (class "Default")
      (node (ref "A20") (pin "H1") (pinfunction "4A_H1") (pintype "input"))
      (node (ref "A21") (pin "K1") (pinfunction "ODD_K1") (pintype "output"))
    )
    (net (code "264") (name "Net-(A20C-4B)") (class "Default")
      (node (ref "A20") (pin "C1") (pinfunction "4B_C1") (pintype "input"))
      (node (ref "A21") (pin "L1") (pinfunction "EVEN_L1") (pintype "output"))
    )
    (net (code "265") (name "Net-(A20C-8A)") (class "Default")
      (node (ref "A20") (pin "J1") (pinfunction "8A_J1") (pintype "input"))
      (node (ref "A21") (pin "U2") (pinfunction "ODD_U2") (pintype "output"))
    )
    (net (code "266") (name "Net-(A20C-8B)") (class "Default")
      (node (ref "A20") (pin "D1") (pinfunction "8B_D1") (pintype "input"))
      (node (ref "A21") (pin "V2") (pinfunction "EVEN_V2") (pintype "output"))
    )
    (net (code "267") (name "Net-(B07A-IN2)") (class "Default")
      (node (ref "B06") (pin "V2") (pinfunction "V2_V2") (pintype "output"))
      (node (ref "B07") (pin "C1") (pinfunction "IN2_C1") (pintype "input"))
    )
    (net (code "268") (name "Net-(B08D-IN)") (class "Default")
      (node (ref "B08") (pin "E2") (pinfunction "IN_E2") (pintype "input"))
      (node (ref "B08") (pin "V1") (pinfunction "IN_V1") (pintype "input"))
      (node (ref "B11") (pin "C1") (pinfunction "OUT_C1") (pintype "output"))
    )
    (net (code "269") (name "Net-(B08P-IN)") (class "Default")
      (node (ref "B08") (pin "S2") (pinfunction "IN_S2") (pintype "input"))
      (node (ref "B11") (pin "S1") (pinfunction "OUT_S1") (pintype "output"))
    )
    (net (code "270") (name "Net-(C3-Pad1)") (class "Default")
      (node (ref "C3") (pin "1") (pinfunction "1_1") (pintype "passive"))
      (node (ref "R1") (pin "2") (pinfunction "2_2") (pintype "passive"))
      (node (ref "R2") (pin "2") (pinfunction "2_2") (pintype "passive"))
      (node (ref "R3") (pin "1") (pinfunction "1_1") (pintype "passive"))
      (node (ref "R4") (pin "2") (pinfunction "2_2") (pintype "passive"))
      (node (ref "R5") (pin "2") (pinfunction "2_2") (pintype "passive"))
      (node (ref "R6") (pin "2") (pinfunction "2_2") (pintype "passive"))
      (node (ref "R8") (pin "2") (pinfunction "2_2") (pintype "passive"))
    )
    (net (code "271") (name "Net-(C5-Pad-)") (class "Default")
      (node (ref "C5") (pin "-") (pinfunction "-_-") (pintype "passive"))
      (node (ref "D1") (pin "A") (pinfunction "A_A") (pintype "passive"))
      (node (ref "R7") (pin "1") (pinfunction "1_1") (pintype "passive"))
    )
    (net (code "272") (name "Net-(S3-S)") (class "Default")
      (node (ref "C4") (pin "-") (pinfunction "-_-") (pintype "passive"))
      (node (ref "R6") (pin "1") (pinfunction "1_1") (pintype "passive"))
      (node (ref "S3") (pin "3") (pinfunction "S_3") (pintype "passive"))
    )
    (net (code "273") (name "SKIP_L") (class "Default")
      (node (ref "A03") (pin "K2") (pinfunction "P$2_K2") (pintype "bidirectional"))
      (node (ref "A04") (pin "U2") (pinfunction "D_U2") (pintype "open_collector"))
      (node (ref "B03") (pin "K2") (pinfunction "P$2_K2") (pintype "bidirectional"))
    )
    (net (code "274") (name "VCC") (class "Default")
      (node (ref "R3") (pin "2") (pinfunction "2_2") (pintype "passive"))
    )
    (net (code "275") (name "unconnected-(A04H-E-PadP2)") (class "Default")
      (node (ref "A04") (pin "P2") (pinfunction "E_P2") (pintype "open_collector"))
    )
    (net (code "276") (name "unconnected-(A05A-E-PadE1)") (class "Default")
      (node (ref "A05") (pin "E1") (pinfunction "E_E1") (pintype "open_collector"))
    )
    (net (code "277") (name "unconnected-(A05G-E-PadL1)") (class "Default")
      (node (ref "A05") (pin "L1") (pinfunction "E_L1") (pintype "open_collector"))
    )
    (net (code "278") (name "unconnected-(A06-PadB1)") (class "Default")
      (node (ref "A06") (pin "B1") (pinfunction "B1_B1") (pintype "output"))
    )
    (net (code "279") (name "unconnected-(A06-PadD1)") (class "Default")
      (node (ref "A06") (pin "D1") (pinfunction "D1_D1") (pintype "output"))
    )
    (net (code "280") (name "unconnected-(A06-PadF1)") (class "Default")
      (node (ref "A06") (pin "F1") (pinfunction "F1_F1") (pintype "output"))
    )
    (net (code "281") (name "unconnected-(A10A-1-PadE1)") (class "Default")
      (node (ref "A10") (pin "E1") (pinfunction "1_E1") (pintype "output"))
    )
    (net (code "282") (name "unconnected-(A10E-1-PadL1)") (class "Default")
      (node (ref "A10") (pin "L1") (pinfunction "1_L1") (pintype "output"))
    )
    (net (code "283") (name "unconnected-(A10G-1-PadS1)") (class "Default")
      (node (ref "A10") (pin "S1") (pinfunction "1_S1") (pintype "output"))
    )
    (net (code "284") (name "unconnected-(A13-PadN2)") (class "Default")
      (node (ref "A13") (pin "N2") (pinfunction "N2_N2") (pintype "passive"))
    )
    (net (code "285") (name "unconnected-(A13-PadP2)") (class "Default")
      (node (ref "A13") (pin "P2") (pinfunction "P2_P2") (pintype "passive"))
    )
    (net (code "286") (name "unconnected-(A13E-F2-PadE2)") (class "Default")
      (node (ref "A13") (pin "E2") (pinfunction "F2_E2") (pintype "output"))
    )
    (net (code "287") (name "unconnected-(A13E-N2-PadJ1)") (class "Default")
      (node (ref "A13") (pin "J1") (pinfunction "N2_J1") (pintype "passive"))
    )
    (net (code "288") (name "unconnected-(A14A-0-PadF1)") (class "Default")
      (node (ref "A14") (pin "F1") (pinfunction "0_F1") (pintype "output"))
    )
    (net (code "289") (name "unconnected-(A14D-0-PadJ2)") (class "Default")
      (node (ref "A14") (pin "J2") (pinfunction "0_J2") (pintype "output"))
    )
    (net (code "290") (name "unconnected-(A14E-1-PadL1)") (class "Default")
      (node (ref "A14") (pin "L1") (pinfunction "1_L1") (pintype "output"))
    )
    (net (code "291") (name "unconnected-(A14F-0-PadR2)") (class "Default")
      (node (ref "A14") (pin "R2") (pinfunction "0_R2") (pintype "output"))
    )
    (net (code "292") (name "unconnected-(A14G-0-PadU1)") (class "Default")
      (node (ref "A14") (pin "U1") (pinfunction "0_U1") (pintype "output"))
    )
    (net (code "293") (name "unconnected-(A19-PadD1)") (class "Default")
      (node (ref "A19") (pin "D1") (pinfunction "D1_D1") (pintype "passive"))
    )
    (net (code "294") (name "unconnected-(A19-PadH1)") (class "Default")
      (node (ref "A19") (pin "H1") (pinfunction "H1_H1") (pintype "passive"))
    )
    (net (code "295") (name "unconnected-(A19-PadJ1)") (class "Default")
      (node (ref "A19") (pin "J1") (pinfunction "J1_J1") (pintype "passive"))
    )
    (net (code "296") (name "unconnected-(A19-PadL2)") (class "Default")
      (node (ref "A19") (pin "L2") (pinfunction "L2_L2") (pintype "passive"))
    )
    (net (code "297") (name "unconnected-(A19D-D1-PadN1)") (class "Default")
      (node (ref "A19") (pin "N1") (pinfunction "D1_N1") (pintype "passive"))
    )
    (net (code "298") (name "unconnected-(A19D-H1-PadS1)") (class "Default")
      (node (ref "A19") (pin "S1") (pinfunction "H1_S1") (pintype "passive"))
    )
    (net (code "299") (name "unconnected-(A19D-J1-PadU1)") (class "Default")
      (node (ref "A19") (pin "U1") (pinfunction "J1_U1") (pintype "passive"))
    )
    (net (code "300") (name "unconnected-(A20C-ODD-PadK1)") (class "Default")
      (node (ref "A20") (pin "K1") (pinfunction "ODD_K1") (pintype "output"))
    )
    (net (code "301") (name "unconnected-(B06-PadB1)") (class "Default")
      (node (ref "B06") (pin "B1") (pinfunction "B1_B1") (pintype "output"))
    )
    (net (code "302") (name "unconnected-(B06-PadD1)") (class "Default")
      (node (ref "B06") (pin "D1") (pinfunction "D1_D1") (pintype "output"))
    )
    (net (code "303") (name "unconnected-(B06-PadF1)") (class "Default")
      (node (ref "B06") (pin "F1") (pinfunction "F1_F1") (pintype "output"))
    )
  )
)
